# Printing.net
KiCad netlist of a schematic drawn in Altium Designer
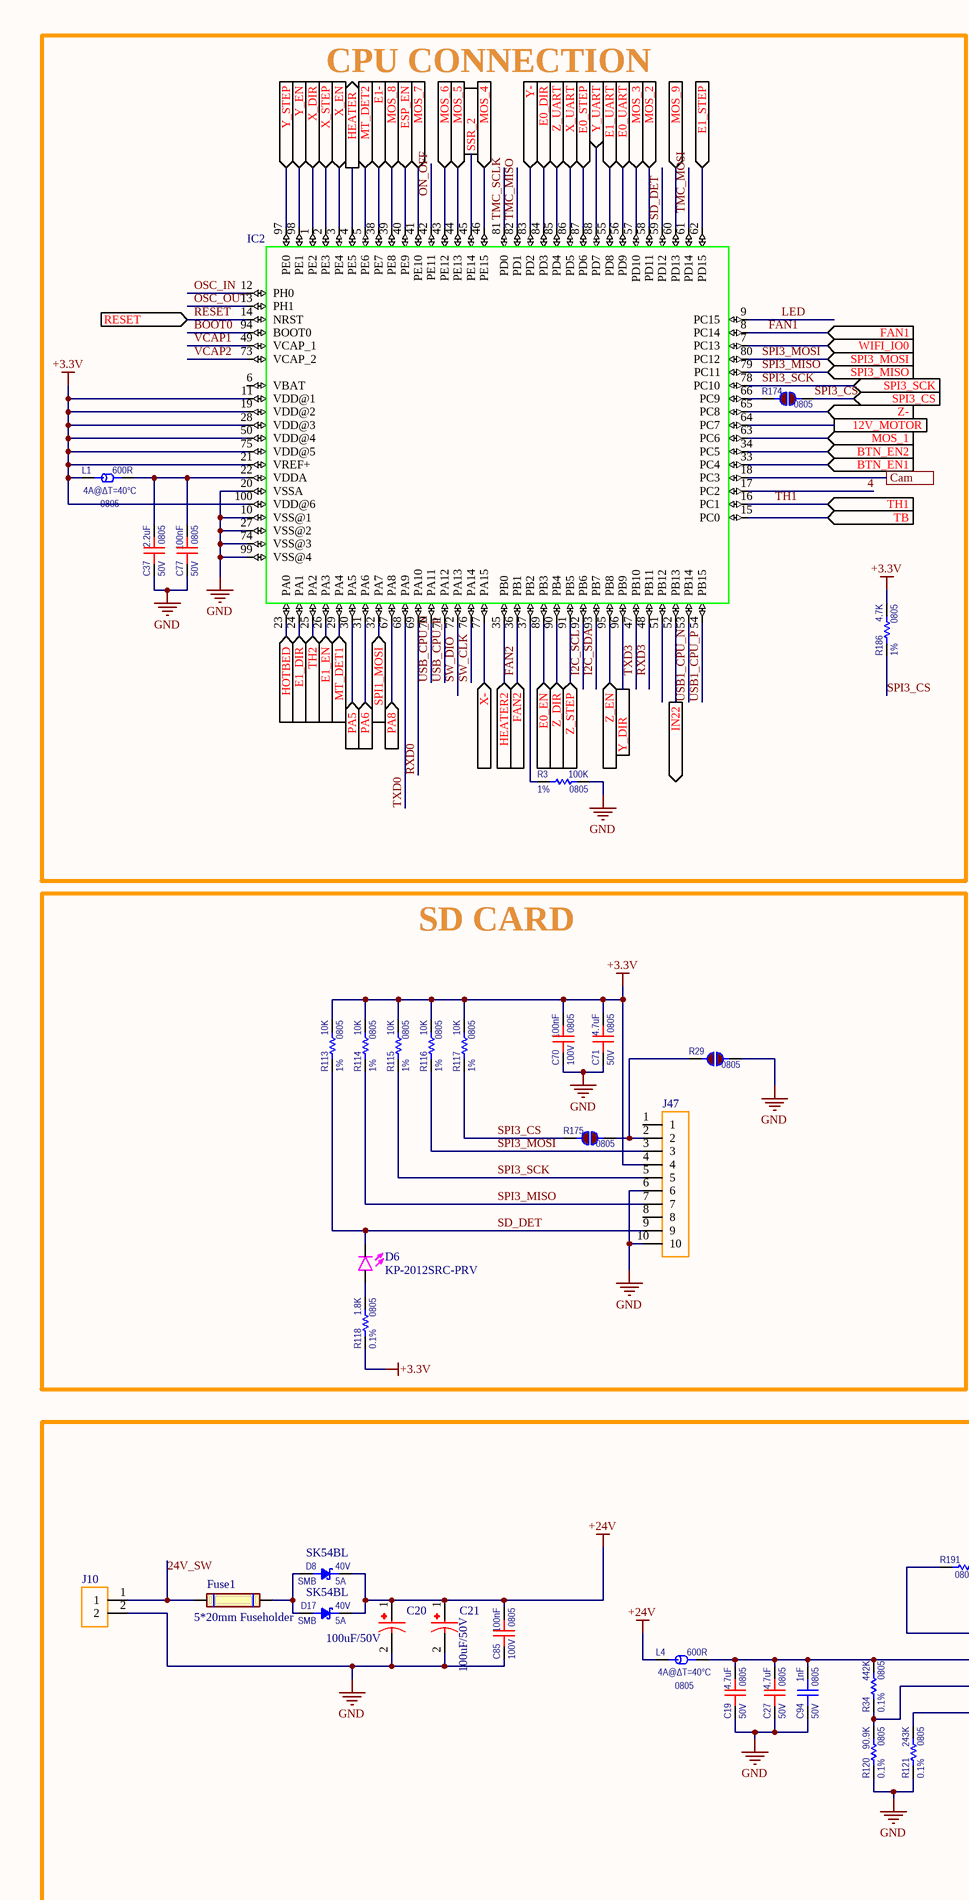
[diagram p0: Printing.SchDoc, left]
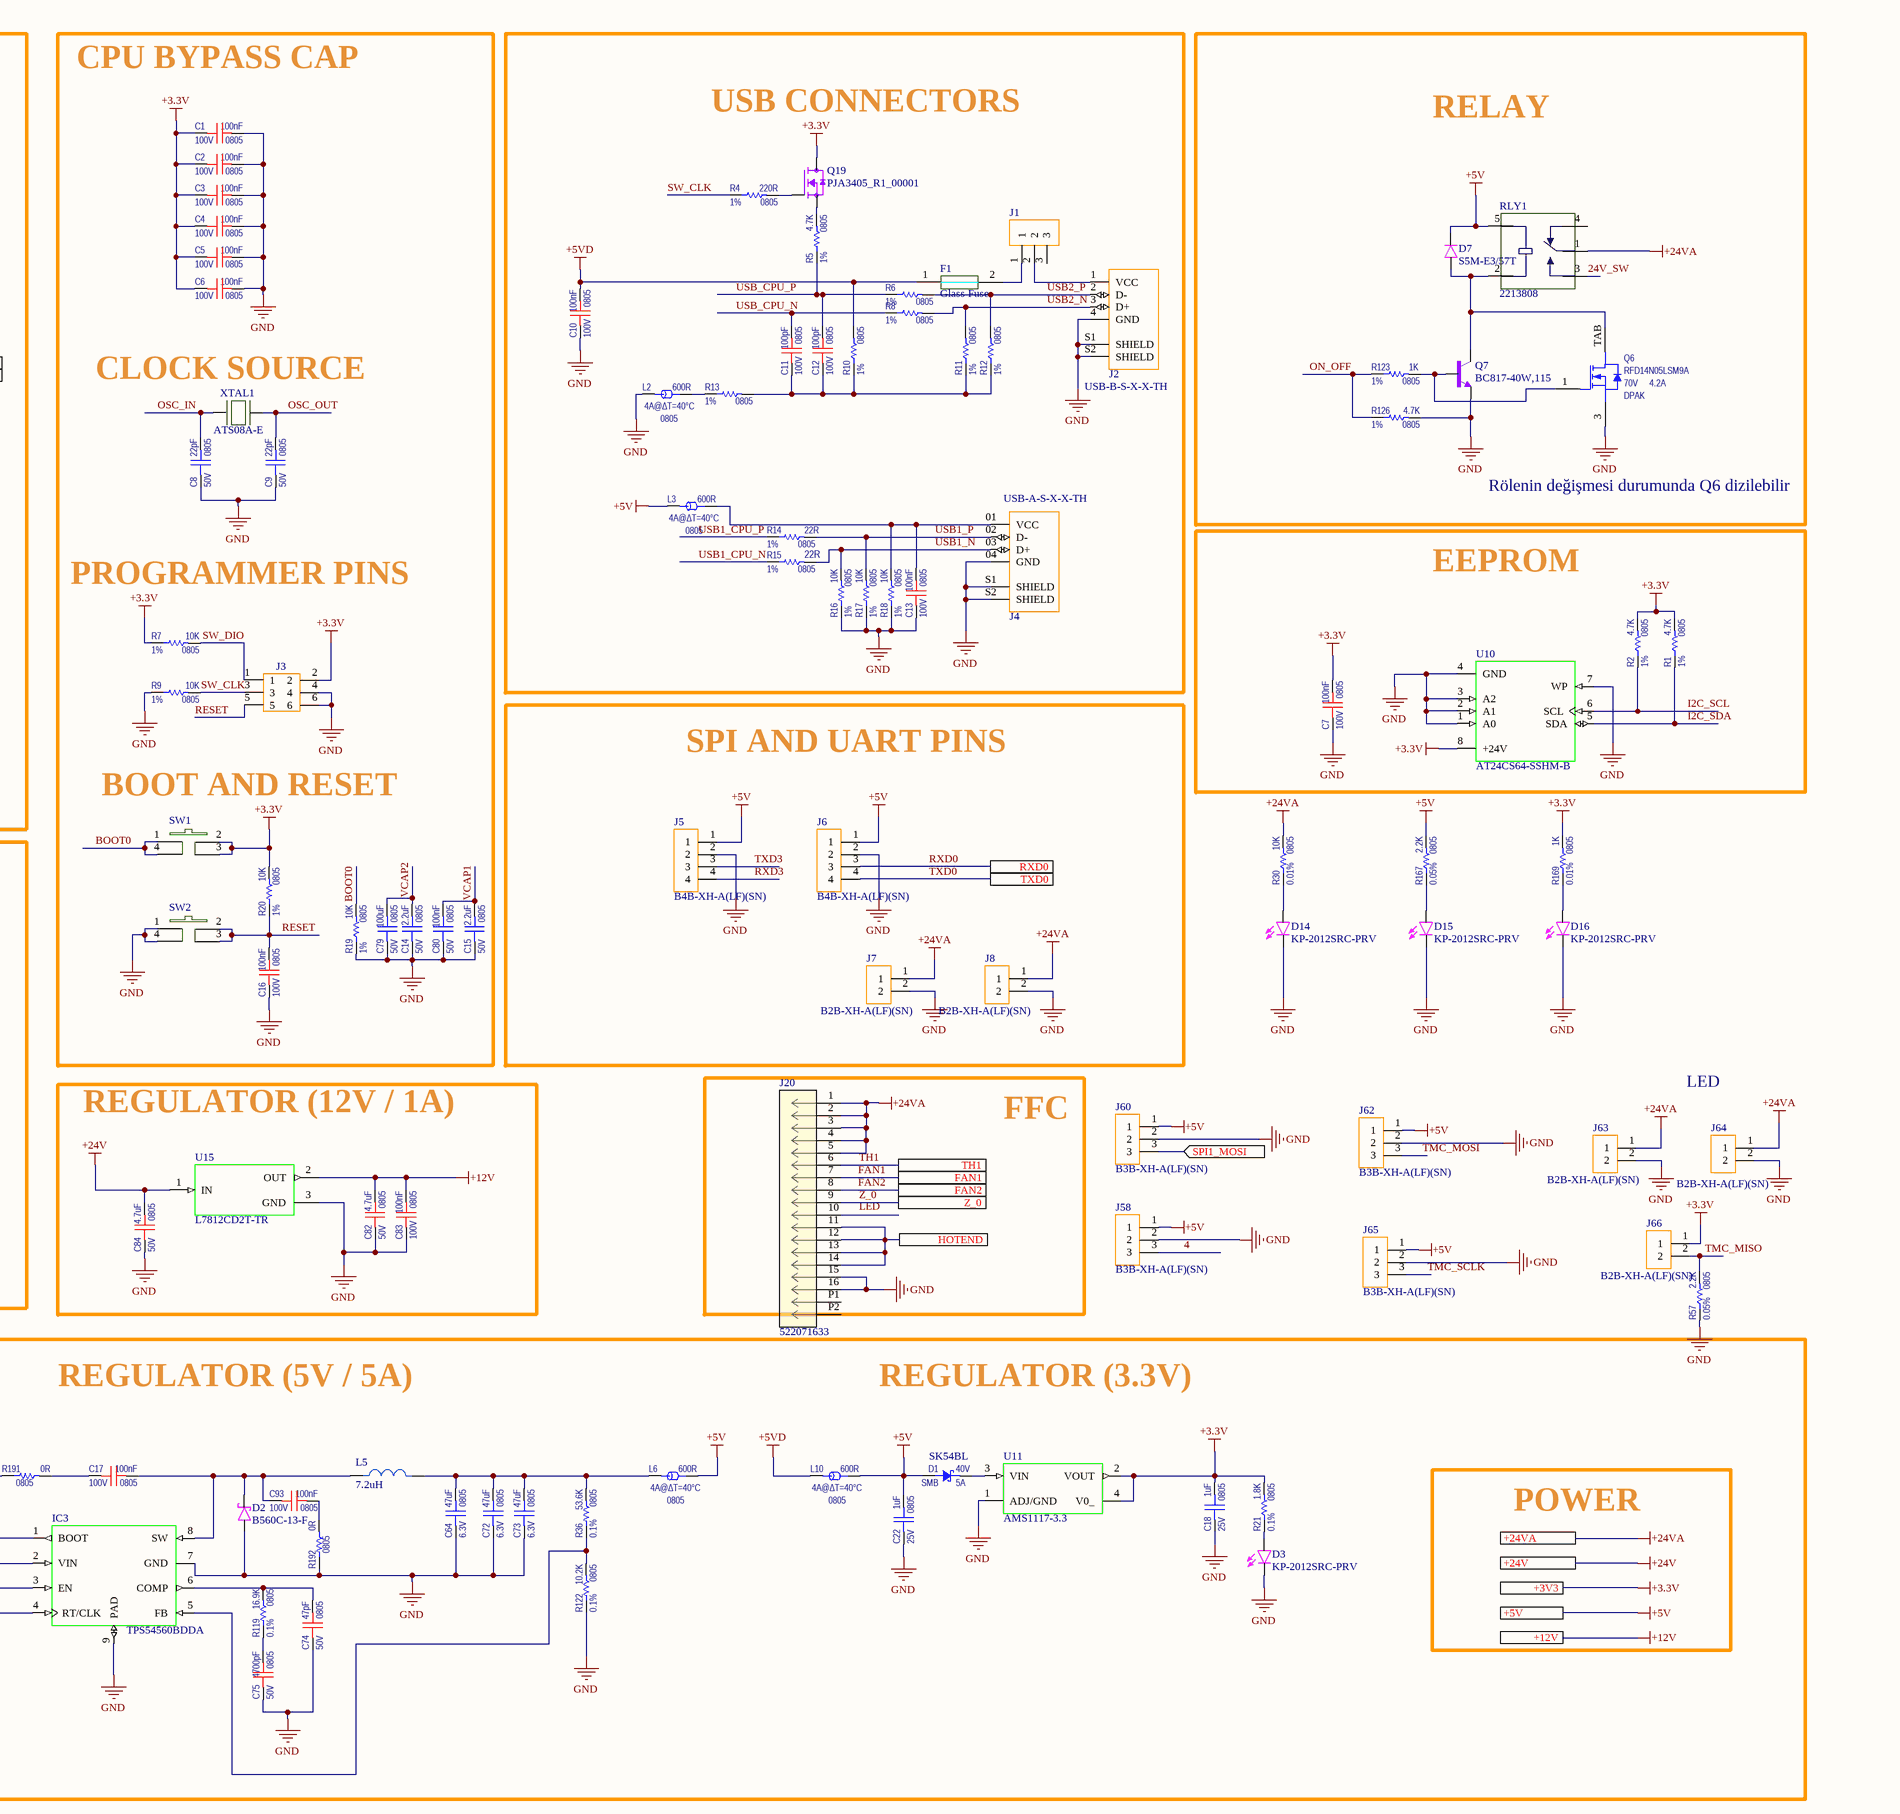
[diagram p1: Printing.SchDoc, right]

(export (version "E")
  (design (tool "Eeschema 10.0.6"))
  (components
    (comp (ref "C1")
      (value "100nF")
      (footprint "C_0805_GEN_1.40H")
      (description "CAP_CER_100nF_100V_X7R_10%_0805")
      (fields
        (field (name "VOLTAGE") "100V")
        (field (name "PACKAGE") "0805")
        (field (name "SIMILAR PART") "C0805C104J1RECAUTO7210; C0805X104J1RECAUTO")
        (field (name "TOLERANCE") "10%")
        (field (name "ADDED BY") "İlhanT")
        (field (name "CHECKED BY") "İlkerU")
      )
      (libsource (lib "FireANTs_HwLibDB") (part "ESDSafeCapacitor"))
    )
    (comp (ref "C2")
      (value "100nF")
      (footprint "C_0805_GEN_1.40H")
      (description "CAP_CER_100nF_100V_X7R_10%_0805")
      (fields
        (field (name "VOLTAGE") "100V")
        (field (name "PACKAGE") "0805")
        (field (name "SIMILAR PART") "C0805C104J1RECAUTO7210; C0805X104J1RECAUTO")
        (field (name "TOLERANCE") "10%")
        (field (name "ADDED BY") "İlhanT")
        (field (name "CHECKED BY") "İlkerU")
      )
      (libsource (lib "FireANTs_HwLibDB") (part "ESDSafeCapacitor"))
    )
    (comp (ref "C3")
      (value "100nF")
      (footprint "C_0805_GEN_1.40H")
      (description "CAP_CER_100nF_100V_X7R_10%_0805")
      (fields
        (field (name "VOLTAGE") "100V")
        (field (name "PACKAGE") "0805")
        (field (name "SIMILAR PART") "C0805C104J1RECAUTO7210; C0805X104J1RECAUTO")
        (field (name "TOLERANCE") "10%")
        (field (name "ADDED BY") "İlhanT")
        (field (name "CHECKED BY") "İlkerU")
      )
      (libsource (lib "FireANTs_HwLibDB") (part "ESDSafeCapacitor"))
    )
    (comp (ref "C4")
      (value "100nF")
      (footprint "C_0805_GEN_1.40H")
      (description "CAP_CER_100nF_100V_X7R_10%_0805")
      (fields
        (field (name "VOLTAGE") "100V")
        (field (name "PACKAGE") "0805")
        (field (name "SIMILAR PART") "C0805C104J1RECAUTO7210; C0805X104J1RECAUTO")
        (field (name "TOLERANCE") "10%")
        (field (name "ADDED BY") "İlhanT")
        (field (name "CHECKED BY") "İlkerU")
      )
      (libsource (lib "FireANTs_HwLibDB") (part "ESDSafeCapacitor"))
    )
    (comp (ref "C5")
      (value "100nF")
      (footprint "C_0805_GEN_1.40H")
      (description "CAP_CER_100nF_100V_X7R_10%_0805")
      (fields
        (field (name "VOLTAGE") "100V")
        (field (name "PACKAGE") "0805")
        (field (name "SIMILAR PART") "C0805C104J1RECAUTO7210; C0805X104J1RECAUTO")
        (field (name "TOLERANCE") "10%")
        (field (name "ADDED BY") "İlhanT")
        (field (name "CHECKED BY") "İlkerU")
      )
      (libsource (lib "FireANTs_HwLibDB") (part "ESDSafeCapacitor"))
    )
    (comp (ref "C6")
      (value "100nF")
      (footprint "C_0805_GEN_1.40H")
      (description "CAP_CER_100nF_100V_X7R_10%_0805")
      (fields
        (field (name "VOLTAGE") "100V")
        (field (name "PACKAGE") "0805")
        (field (name "SIMILAR PART") "C0805C104J1RECAUTO7210; C0805X104J1RECAUTO")
        (field (name "TOLERANCE") "10%")
        (field (name "ADDED BY") "İlhanT")
        (field (name "CHECKED BY") "İlkerU")
      )
      (libsource (lib "FireANTs_HwLibDB") (part "ESDSafeCapacitor"))
    )
    (comp (ref "C7")
      (value "100nF")
      (footprint "C_0805_GEN_1.40H")
      (description "CAP_CER_100nF_100V_X7R_10%_0805")
      (fields
        (field (name "VOLTAGE") "100V")
        (field (name "PACKAGE") "0805")
        (field (name "SIMILAR PART") "C0805C104J1RECAUTO7210; C0805X104J1RECAUTO")
        (field (name "TOLERANCE") "10%")
        (field (name "ADDED BY") "İlhanT")
        (field (name "CHECKED BY") "İlkerU")
      )
      (libsource (lib "FireANTs_HwLibDB") (part "ESDSafeCapacitor"))
    )
    (comp (ref "C8")
      (value "22pF")
      (footprint "C_0805_GEN_1.10H")
      (description "CAP_CER_22pF_50V_X5R_5%_0805")
      (fields
        (field (name "VOLTAGE") "50V")
        (field (name "PACKAGE") "0805")
        (field (name "TOLERANCE") "5%")
        (field (name "Comment") "Capacitor")
        (field (name "ADDED BY") "HicabiB")
        (field (name "CHECKED BY") "???")
      )
      (libsource (lib "FireANTs_HwLibDB") (part "Capacitor"))
    )
    (comp (ref "C9")
      (value "22pF")
      (footprint "C_0805_GEN_1.10H")
      (description "CAP_CER_22pF_50V_X5R_5%_0805")
      (fields
        (field (name "VOLTAGE") "50V")
        (field (name "PACKAGE") "0805")
        (field (name "TOLERANCE") "5%")
        (field (name "Comment") "Capacitor")
        (field (name "ADDED BY") "HicabiB")
        (field (name "CHECKED BY") "???")
      )
      (libsource (lib "FireANTs_HwLibDB") (part "Capacitor"))
    )
    (comp (ref "C10")
      (value "100nF")
      (footprint "C_0805_GEN_1.40H")
      (description "CAP_CER_100nF_100V_X7R_10%_0805")
      (fields
        (field (name "VOLTAGE") "100V")
        (field (name "PACKAGE") "0805")
        (field (name "SIMILAR PART") "C0805C104J1RECAUTO7210; C0805X104J1RECAUTO")
        (field (name "TOLERANCE") "10%")
        (field (name "ADDED BY") "İlhanT")
        (field (name "CHECKED BY") "İlkerU")
      )
      (libsource (lib "FireANTs_HwLibDB") (part "ESDSafeCapacitor"))
    )
    (comp (ref "C11")
      (value "100pF")
      (footprint "C_0805_GEN_1.40H")
      (description "CAP_CER_100nF_100V_X7R_10%_0805")
      (fields
        (field (name "VOLTAGE") "100V")
        (field (name "PACKAGE") "0805")
        (field (name "SIMILAR PART") "C0805C104J1RECAUTO7210; C0805X104J1RECAUTO")
        (field (name "TOLERANCE") "10%")
        (field (name "ADDED BY") "İlhanT")
        (field (name "CHECKED BY") "İlkerU")
      )
      (libsource (lib "FireANTs_HwLibDB") (part "ESDSafeCapacitor"))
    )
    (comp (ref "C12")
      (value "100pF")
      (footprint "C_0805_GEN_1.40H")
      (description "CAP_CER_100nF_100V_X7R_10%_0805")
      (fields
        (field (name "VOLTAGE") "100V")
        (field (name "PACKAGE") "0805")
        (field (name "SIMILAR PART") "C0805C104J1RECAUTO7210; C0805X104J1RECAUTO")
        (field (name "TOLERANCE") "10%")
        (field (name "ADDED BY") "İlhanT")
        (field (name "CHECKED BY") "İlkerU")
      )
      (libsource (lib "FireANTs_HwLibDB") (part "ESDSafeCapacitor"))
    )
    (comp (ref "C13")
      (value "100nF")
      (footprint "C_0805_GEN_1.40H")
      (description "CAP_CER_100nF_100V_X7R_10%_0805")
      (fields
        (field (name "VOLTAGE") "100V")
        (field (name "PACKAGE") "0805")
        (field (name "SIMILAR PART") "C0805C104J1RECAUTO7210; C0805X104J1RECAUTO")
        (field (name "TOLERANCE") "10%")
        (field (name "ADDED BY") "İlhanT")
        (field (name "CHECKED BY") "İlkerU")
      )
      (libsource (lib "FireANTs_HwLibDB") (part "ESDSafeCapacitor"))
    )
    (comp (ref "C14")
      (value "2.2uF")
      (footprint "C_0805_GEN_1.40H")
      (description "CAP_CER_2.2uF_50V_X5R_10%_0805")
      (fields
        (field (name "VOLTAGE") "50V")
        (field (name "PACKAGE") "0805")
        (field (name "TOLERANCE") "10%")
        (field (name "Comment") "Capacitor")
        (field (name "ADDED BY") "HicabiB")
        (field (name "CHECKED BY") "???")
      )
      (libsource (lib "FireANTs_HwLibDB") (part "Capacitor"))
    )
    (comp (ref "C15")
      (value "2.2uF")
      (footprint "C_0805_GEN_1.40H")
      (description "CAP_CER_2.2uF_50V_X5R_10%_0805")
      (fields
        (field (name "VOLTAGE") "50V")
        (field (name "PACKAGE") "0805")
        (field (name "TOLERANCE") "10%")
        (field (name "Comment") "Capacitor")
        (field (name "ADDED BY") "HicabiB")
        (field (name "CHECKED BY") "???")
      )
      (libsource (lib "FireANTs_HwLibDB") (part "Capacitor"))
    )
    (comp (ref "C16")
      (value "100nF")
      (footprint "C_0805_GEN_1.40H")
      (description "CAP_CER_100nF_100V_X7R_10%_0805")
      (fields
        (field (name "VOLTAGE") "100V")
        (field (name "PACKAGE") "0805")
        (field (name "SIMILAR PART") "C0805C104J1RECAUTO7210; C0805X104J1RECAUTO")
        (field (name "TOLERANCE") "10%")
        (field (name "ADDED BY") "İlhanT")
        (field (name "CHECKED BY") "İlkerU")
      )
      (libsource (lib "FireANTs_HwLibDB") (part "ESDSafeCapacitor"))
    )
    (comp (ref "C17")
      (value "100nF")
      (footprint "C_0805_GEN_1.40H")
      (description "CAP_CER_100nF_100V_X7R_10%_0805")
      (fields
        (field (name "VOLTAGE") "100V")
        (field (name "PACKAGE") "0805")
        (field (name "SIMILAR PART") "C0805C104J1RECAUTO7210; C0805X104J1RECAUTO")
        (field (name "TOLERANCE") "10%")
        (field (name "ADDED BY") "İlhanT")
        (field (name "CHECKED BY") "İlkerU")
      )
      (libsource (lib "FireANTs_HwLibDB") (part "ESDSafeCapacitor"))
    )
    (comp (ref "C18")
      (value "1uF")
      (footprint "C_0805_GEN_1.40H")
      (description "CAP_CER_1uF_25V_X7R_10%_0805")
      (fields
        (field (name "VOLTAGE") "25V")
        (field (name "PACKAGE") "0805")
        (field (name "SIMILAR PART") "CGA4J3X7R1E105K125AB")
        (field (name "TOLERANCE") "10%")
        (field (name "ADDED BY") "SonerI")
        (field (name "CHECKED BY") "İlkerU")
      )
      (libsource (lib "FireANTs_HwLibDB") (part "Capacitor"))
    )
    (comp (ref "C19")
      (value "4.7uF")
      (footprint "C_0805_GEN_1.40H")
      (description "CAP_CER_100nF_100V_X7R_10%_0805")
      (fields
        (field (name "VOLTAGE") "50V")
        (field (name "PACKAGE") "0805")
        (field (name "SIMILAR PART") "C0805C104J1RECAUTO7210; C0805X104J1RECAUTO")
        (field (name "TOLERANCE") "10%")
        (field (name "ADDED BY") "İlhanT")
        (field (name "CHECKED BY") "İlkerU")
      )
      (libsource (lib "FireANTs_HwLibDB") (part "ESDSafeCapacitor"))
    )
    (comp (ref "C20")
      (value "100uF/50V")
      (footprint "SC1V107M6L07KVR")
      (libsource (lib "Printing") (part "SC1V107M6L07KVR"))
    )
    (comp (ref "C21")
      (value "100uF/50V")
      (footprint "SC1V107M6L07KVR")
      (libsource (lib "Printing") (part "SC1V107M6L07KVR"))
    )
    (comp (ref "C22")
      (value "1uF")
      (footprint "C_0805_GEN_1.40H")
      (description "CAP_CER_1uF_25V_X7R_10%_0805")
      (fields
        (field (name "VOLTAGE") "25V")
        (field (name "PACKAGE") "0805")
        (field (name "SIMILAR PART") "CGA4J3X7R1E105K125AB")
        (field (name "TOLERANCE") "10%")
        (field (name "ADDED BY") "SonerI")
        (field (name "CHECKED BY") "İlkerU")
      )
      (libsource (lib "FireANTs_HwLibDB") (part "Capacitor"))
    )
    (comp (ref "C27")
      (value "4.7uF")
      (footprint "C_0805_GEN_1.40H")
      (description "CAP_CER_100nF_100V_X7R_10%_0805")
      (fields
        (field (name "VOLTAGE") "50V")
        (field (name "PACKAGE") "0805")
        (field (name "SIMILAR PART") "C0805C104J1RECAUTO7210; C0805X104J1RECAUTO")
        (field (name "TOLERANCE") "10%")
        (field (name "ADDED BY") "İlhanT")
        (field (name "CHECKED BY") "İlkerU")
      )
      (libsource (lib "FireANTs_HwLibDB") (part "ESDSafeCapacitor"))
    )
    (comp (ref "C37")
      (value "2.2uF")
      (footprint "C_0805_GEN_1.40H")
      (description "CAP_CER_100nF_100V_X7R_10%_0805")
      (fields
        (field (name "VOLTAGE") "50V")
        (field (name "PACKAGE") "0805")
        (field (name "SIMILAR PART") "C0805C104J1RECAUTO7210; C0805X104J1RECAUTO")
        (field (name "TOLERANCE") "10%")
        (field (name "ADDED BY") "İlhanT")
        (field (name "CHECKED BY") "İlkerU")
      )
      (libsource (lib "FireANTs_HwLibDB") (part "ESDSafeCapacitor"))
    )
    (comp (ref "C64")
      (value "47uF")
      (footprint "C_0805_GEN_1.40H")
      (description "CAP_CER_47uF_6.3V_X5R_20%_0805")
      (fields
        (field (name "VOLTAGE") "6.3V")
        (field (name "PACKAGE") "0805")
        (field (name "SIMILAR PART") "JMK212BBJ476MG-T")
        (field (name "TOLERANCE") "20%")
        (field (name "ADDED BY") "HasanA")
        (field (name "CHECKED BY") "İlkerU")
      )
      (libsource (lib "FireANTs_HwLibDB") (part "Capacitor"))
    )
    (comp (ref "C70")
      (value "100nF")
      (footprint "C_0805_GEN_1.40H")
      (description "CAP_CER_100nF_100V_X7R_10%_0805")
      (fields
        (field (name "VOLTAGE") "100V")
        (field (name "PACKAGE") "0805")
        (field (name "SIMILAR PART") "C0805C104J1RECAUTO7210; C0805X104J1RECAUTO")
        (field (name "TOLERANCE") "10%")
        (field (name "ADDED BY") "İlhanT")
        (field (name "CHECKED BY") "İlkerU")
      )
      (libsource (lib "FireANTs_HwLibDB") (part "ESDSafeCapacitor"))
    )
    (comp (ref "C71")
      (value "4.7uF")
      (footprint "C_0805_GEN_1.40H")
      (description "CAP_CER_100nF_100V_X7R_10%_0805")
      (fields
        (field (name "VOLTAGE") "50V")
        (field (name "PACKAGE") "0805")
        (field (name "SIMILAR PART") "C0805C104J1RECAUTO7210; C0805X104J1RECAUTO")
        (field (name "TOLERANCE") "10%")
        (field (name "ADDED BY") "İlhanT")
        (field (name "CHECKED BY") "İlkerU")
      )
      (libsource (lib "FireANTs_HwLibDB") (part "ESDSafeCapacitor"))
    )
    (comp (ref "C72")
      (value "47uF")
      (footprint "C_0805_GEN_1.40H")
      (description "CAP_CER_47uF_6.3V_X5R_20%_0805")
      (fields
        (field (name "VOLTAGE") "6.3V")
        (field (name "PACKAGE") "0805")
        (field (name "SIMILAR PART") "JMK212BBJ476MG-T")
        (field (name "TOLERANCE") "20%")
        (field (name "ADDED BY") "HasanA")
        (field (name "CHECKED BY") "İlkerU")
      )
      (libsource (lib "FireANTs_HwLibDB") (part "Capacitor"))
    )
    (comp (ref "C73")
      (value "47uF")
      (footprint "C_0805_GEN_1.40H")
      (description "CAP_CER_47uF_6.3V_X5R_20%_0805")
      (fields
        (field (name "VOLTAGE") "6.3V")
        (field (name "PACKAGE") "0805")
        (field (name "SIMILAR PART") "JMK212BBJ476MG-T")
        (field (name "TOLERANCE") "20%")
        (field (name "ADDED BY") "HasanA")
        (field (name "CHECKED BY") "İlkerU")
      )
      (libsource (lib "FireANTs_HwLibDB") (part "Capacitor"))
    )
    (comp (ref "C74")
      (value "47pF")
      (footprint "C_0805_GEN_1.40H")
      (description "CAP_CER_100nF_100V_X7R_10%_0805")
      (fields
        (field (name "VOLTAGE") "50V")
        (field (name "PACKAGE") "0805")
        (field (name "SIMILAR PART") "C0805C104J1RECAUTO7210; C0805X104J1RECAUTO")
        (field (name "TOLERANCE") "10%")
        (field (name "ADDED BY") "İlhanT")
        (field (name "CHECKED BY") "İlkerU")
      )
      (libsource (lib "FireANTs_HwLibDB") (part "ESDSafeCapacitor"))
    )
    (comp (ref "C75")
      (value "4700pF")
      (footprint "C_0805_GEN_1.40H")
      (description "CAP_CER_100nF_100V_X7R_10%_0805")
      (fields
        (field (name "VOLTAGE") "50V")
        (field (name "PACKAGE") "0805")
        (field (name "SIMILAR PART") "C0805C104J1RECAUTO7210; C0805X104J1RECAUTO")
        (field (name "TOLERANCE") "10%")
        (field (name "ADDED BY") "İlhanT")
        (field (name "CHECKED BY") "İlkerU")
      )
      (libsource (lib "FireANTs_HwLibDB") (part "ESDSafeCapacitor"))
    )
    (comp (ref "C77")
      (value "100nF")
      (footprint "C_0805_GEN_1.40H")
      (description "CAP_CER_100nF_100V_X7R_10%_0805")
      (fields
        (field (name "VOLTAGE") "50V")
        (field (name "PACKAGE") "0805")
        (field (name "SIMILAR PART") "C0805C104J1RECAUTO7210; C0805X104J1RECAUTO")
        (field (name "TOLERANCE") "10%")
        (field (name "ADDED BY") "İlhanT")
        (field (name "CHECKED BY") "İlkerU")
      )
      (libsource (lib "FireANTs_HwLibDB") (part "ESDSafeCapacitor"))
    )
    (comp (ref "C79")
      (value "100uF")
      (footprint "C_0805_GEN_1.40H")
      (description "CAP_CER_2.2uF_50V_X5R_10%_0805")
      (fields
        (field (name "VOLTAGE") "50V")
        (field (name "PACKAGE") "0805")
        (field (name "TOLERANCE") "10%")
        (field (name "Comment") "Capacitor")
        (field (name "ADDED BY") "HicabiB")
        (field (name "CHECKED BY") "???")
      )
      (libsource (lib "FireANTs_HwLibDB") (part "Capacitor"))
    )
    (comp (ref "C80")
      (value "100nF")
      (footprint "C_0805_GEN_1.40H")
      (description "CAP_CER_2.2uF_50V_X5R_10%_0805")
      (fields
        (field (name "VOLTAGE") "50V")
        (field (name "PACKAGE") "0805")
        (field (name "TOLERANCE") "10%")
        (field (name "Comment") "Capacitor")
        (field (name "ADDED BY") "HicabiB")
        (field (name "CHECKED BY") "???")
      )
      (libsource (lib "FireANTs_HwLibDB") (part "Capacitor"))
    )
    (comp (ref "C82")
      (value "4.7uF")
      (footprint "C_0805_GEN_1.40H")
      (description "CAP_CER_100nF_100V_X7R_10%_0805")
      (fields
        (field (name "VOLTAGE") "50V")
        (field (name "PACKAGE") "0805")
        (field (name "SIMILAR PART") "C0805C104J1RECAUTO7210; C0805X104J1RECAUTO")
        (field (name "TOLERANCE") "10%")
        (field (name "ADDED BY") "İlhanT")
        (field (name "CHECKED BY") "İlkerU")
      )
      (libsource (lib "FireANTs_HwLibDB") (part "ESDSafeCapacitor"))
    )
    (comp (ref "C83")
      (value "100nF")
      (footprint "C_0805_GEN_1.40H")
      (description "CAP_CER_100nF_100V_X7R_10%_0805")
      (fields
        (field (name "VOLTAGE") "100V")
        (field (name "PACKAGE") "0805")
        (field (name "SIMILAR PART") "C0805C104J1RECAUTO7210; C0805X104J1RECAUTO")
        (field (name "TOLERANCE") "10%")
        (field (name "ADDED BY") "İlhanT")
        (field (name "CHECKED BY") "İlkerU")
      )
      (libsource (lib "FireANTs_HwLibDB") (part "ESDSafeCapacitor"))
    )
    (comp (ref "C84")
      (value "4.7uF")
      (footprint "C_0805_GEN_1.40H")
      (description "CAP_CER_100nF_100V_X7R_10%_0805")
      (fields
        (field (name "VOLTAGE") "50V")
        (field (name "PACKAGE") "0805")
        (field (name "SIMILAR PART") "C0805C104J1RECAUTO7210; C0805X104J1RECAUTO")
        (field (name "TOLERANCE") "10%")
        (field (name "ADDED BY") "İlhanT")
        (field (name "CHECKED BY") "İlkerU")
      )
      (libsource (lib "FireANTs_HwLibDB") (part "ESDSafeCapacitor"))
    )
    (comp (ref "C85")
      (value "100nF")
      (footprint "C_0805_GEN_1.40H")
      (description "CAP_CER_100nF_100V_X7R_10%_0805")
      (fields
        (field (name "VOLTAGE") "100V")
        (field (name "PACKAGE") "0805")
        (field (name "SIMILAR PART") "C0805C104J1RECAUTO7210; C0805X104J1RECAUTO")
        (field (name "TOLERANCE") "10%")
        (field (name "ADDED BY") "İlhanT")
        (field (name "CHECKED BY") "İlkerU")
      )
      (libsource (lib "FireANTs_HwLibDB") (part "ESDSafeCapacitor"))
    )
    (comp (ref "C93")
      (value "100nF")
      (footprint "C_0805_GEN_1.40H")
      (description "CAP_CER_100nF_100V_X7R_10%_0805")
      (fields
        (field (name "VOLTAGE") "100V")
        (field (name "PACKAGE") "0805")
        (field (name "SIMILAR PART") "C0805C104J1RECAUTO7210; C0805X104J1RECAUTO")
        (field (name "TOLERANCE") "10%")
        (field (name "ADDED BY") "İlhanT")
        (field (name "CHECKED BY") "İlkerU")
      )
      (libsource (lib "FireANTs_HwLibDB") (part "ESDSafeCapacitor"))
    )
    (comp (ref "C94")
      (value "1nF")
      (footprint "C_0805_GEN_0.70H")
      (description "CAP_CER_1nF_50V_NP0_1%_0805")
      (fields
        (field (name "VOLTAGE") "50V")
        (field (name "PACKAGE") "0805")
        (field (name "SIMILAR PART") "08055A102FAT2A")
        (field (name "TOLERANCE") "1%")
        (field (name "ADDED BY") "İlhanT")
        (field (name "CHECKED BY") "İlkerU")
      )
      (libsource (lib "FireANTs_HwLibDB") (part "Capacitor"))
    )
    (comp (ref "D1")
      (value "SK54BL")
      (footprint "SMB_NRVBS360BT3G")
      (description "DIO_SCHO_SING_60V_3A_SMB")
      (fields
        (field (name "VOLTAGE") "40V")
        (field (name "CURRENT") "5A")
        (field (name "PACKAGE") "SMB")
        (field (name "SIMILAR PART") "STPS3H100UFY")
        (field (name "TOLERANCE") "X")
        (field (name "ADDED BY") "SonerI")
        (field (name "CHECKED BY") "ErayC")
      )
      (libsource (lib "FireANTs_HwLibDB") (part "SchDiode_A2C1"))
    )
    (comp (ref "D2")
      (value "B560C-13-F")
      (footprint "B560C-13-F")
      (description "VR=60V IF=5A 300pF")
      (fields (field (name "MANUFACTURER") "Diodes"))
      (libsource (lib "Printing") (part "B560C-13-F"))
    )
    (comp (ref "D3")
      (value "KP-2012SRC-PRV")
      (footprint "0805 LED")
      (description "KP-2012SRC-PRV Red LED, 640 nm 2012 (0805), Rectangle Lens SMD package")
      (fields (field (name "MANUFACTURER") "Kingbright"))
      (libsource (lib "Printing") (part "KP-2012SRC-PRV"))
    )
    (comp (ref "D6")
      (value "KP-2012SRC-PRV")
      (footprint "0805 LED")
      (description "KP-2012SRC-PRV Red LED, 640 nm 2012 (0805), Rectangle Lens SMD package")
      (fields (field (name "MANUFACTURER") "Kingbright"))
      (libsource (lib "Printing") (part "KP-2012SRC-PRV"))
    )
    (comp (ref "D7")
      (value "S5M-E3/57T")
      (footprint "B560C-13-F")
      (fields (field (name "MANUFACTURER") "Vishay Semiconductors") (field (name "VOLTAGE") "1kV"))
      (libsource (lib "Printing") (part "S5M-E3/57T"))
    )
    (comp (ref "D8")
      (value "SK54BL")
      (footprint "SMB_NRVBS360BT3G")
      (description "DIO_SCHO_SING_60V_3A_SMB")
      (fields
        (field (name "VOLTAGE") "40V")
        (field (name "CURRENT") "5A")
        (field (name "PACKAGE") "SMB")
        (field (name "SIMILAR PART") "STPS3H100UFY")
        (field (name "TOLERANCE") "X")
        (field (name "ADDED BY") "SonerI")
        (field (name "CHECKED BY") "ErayC")
      )
      (libsource (lib "FireANTs_HwLibDB") (part "SchDiode_A2C1"))
    )
    (comp (ref "D14")
      (value "KP-2012SRC-PRV")
      (footprint "0805 LED")
      (description "KP-2012SRC-PRV Red LED, 640 nm 2012 (0805), Rectangle Lens SMD package")
      (fields (field (name "MANUFACTURER") "Kingbright"))
      (libsource (lib "Printing") (part "KP-2012SRC-PRV"))
    )
    (comp (ref "D15")
      (value "KP-2012SRC-PRV")
      (footprint "0805 LED")
      (description "KP-2012SRC-PRV Red LED, 640 nm 2012 (0805), Rectangle Lens SMD package")
      (fields (field (name "MANUFACTURER") "Kingbright"))
      (libsource (lib "Printing") (part "KP-2012SRC-PRV"))
    )
    (comp (ref "D16")
      (value "KP-2012SRC-PRV")
      (footprint "0805 LED")
      (description "KP-2012SRC-PRV Red LED, 640 nm 2012 (0805), Rectangle Lens SMD package")
      (fields (field (name "MANUFACTURER") "Kingbright"))
      (libsource (lib "Printing") (part "KP-2012SRC-PRV"))
    )
    (comp (ref "D17")
      (value "SK54BL")
      (footprint "SMB_NRVBS360BT3G")
      (description "DIO_SCHO_SING_60V_3A_SMB")
      (fields
        (field (name "VOLTAGE") "40V")
        (field (name "CURRENT") "5A")
        (field (name "PACKAGE") "SMB")
        (field (name "SIMILAR PART") "STPS3H100UFY")
        (field (name "TOLERANCE") "X")
        (field (name "ADDED BY") "SonerI")
        (field (name "CHECKED BY") "ErayC")
      )
      (libsource (lib "FireANTs_HwLibDB") (part "SchDiode_A2C1"))
    )
    (comp (ref "F1")
      (value "Glass Fuse")
      (footprint "2410 Sigorta")
      (libsource (lib "Printing") (part "Glass Fuse"))
    )
    (comp (ref "Fuse1")
      (value "5*20mm Fuseholder")
      (footprint "696310001002")
      (description "Fuse Holder 20 A 250V 1 Circuit Cartridge Through Hole")
      (fields (field (name "MF") "Wurth Elektronik") (field (name "MP") "696310001002"))
      (libsource (lib "Printing") (part "696310001002"))
    )
    (comp (ref "IC2")
      (value "MCU-STM32F407VET6(LQFP100)")
      (footprint "LQFP100-0.5-13.8X13.8MM")
      (description "ARMÂ® CortexÂ®-M4 STM32F4 Microcontroller IC 32-Bit 168MHz 512KB _512K x 8_ FLASH 100-LQFP _14x14_")
      (fields (field (name "MF") "STMicroelectronics") (field (name "MP") "STM32F407VET6"))
      (libsource (lib "Printing") (part "MCU-STM32F407VET6(LQFP100)"))
    )
    (comp (ref "IC3")
      (value "TPS54560BDDA")
      (footprint "VREG_LM5017MR/NOPB")
      (description "4.5-V to 60-V input, 5-A, step-down DC-DC converter with Eco-mode 8-SO PowerPAD -40 to 150")
      (fields (field (name "MF") "Texas Instruments"))
      (libsource (lib "Printing") (part "TPS54560BDDA"))
    )
    (comp (ref "J1")
      (value "L-KLS1-207-1-03-S")
      (footprint "L-KLS1-207-1-03-S")
      (libsource (lib "Printing") (part "L-KLS1-207-1-03-S"))
    )
    (comp (ref "J2")
      (value "USB-B-S-X-X-TH")
      (footprint "SAMTEC_USB-B-S-X-X-TH")
      (description "USB-B (USB TYPE-B) USB 2.0 Receptacle Connector 4 Position Through Hole, Right Angle")
      (libsource (lib "Printing") (part "USB-B-S-X-X-TH"))
    )
    (comp (ref "J3")
      (value "5PH1SDA25-203G0NNBL-3X6")
      (footprint "5PH1SDA25-203G0NNBL-3X6")
      (libsource (lib "Printing") (part "5PH1SDA25-203G0NNBL-3X6"))
    )
    (comp (ref "J4")
      (value "USB-A-S-X-X-TH")
      (footprint "SAMTEC_USB-A-S-X-X-TH")
      (description "USB-A (USB TYPE-A) USB 2.0 Receptacle Connector 4 Position Through Hole, Right Angle")
      (fields (field (name "MP") "USB-A-S-S-W-TH") (field (name "DIGI-KEY_PART_NUMBER") "SAM10373-ND"))
      (libsource (lib "Printing") (part "USB-A-S-X-X-TH"))
    )
    (comp (ref "J5")
      (value "B4B-XH-A(LF)(SN)")
      (footprint "JST_B4B-XH-A(LF)(SN)")
      (libsource (lib "Printing") (part "B4B-XH-A(LF)(SN)"))
    )
    (comp (ref "J6")
      (value "B4B-XH-A(LF)(SN)")
      (footprint "JST_B4B-XH-A(LF)(SN)")
      (libsource (lib "Printing") (part "B4B-XH-A(LF)(SN)"))
    )
    (comp (ref "J7")
      (value "B2B-XH-A(LF)(SN)")
      (footprint "JST_B2B-XH-A(LF)(SN)")
      (description "Connector Header Through Hole 2 position 0.098 (2.50mm)")
      (fields (field (name "MF") "JST Sales"))
      (libsource (lib "Printing") (part "B2B-XH-A(LF)(SN)"))
    )
    (comp (ref "J8")
      (value "B2B-XH-A(LF)(SN)")
      (footprint "JST_B2B-XH-A(LF)(SN)")
      (description "Connector Header Through Hole 2 position 0.098 (2.50mm)")
      (fields (field (name "MF") "JST Sales"))
      (libsource (lib "Printing") (part "B2B-XH-A(LF)(SN)"))
    )
    (comp (ref "J10")
      (value "5.08 Klemens")
      (footprint "5.08 Klemens")
      (libsource (lib "Printing") (part "5.08 Klemens"))
    )
    (comp (ref "J20")
      (value "522071633")
      (footprint "CON_522071633_MOL")
      (description "No Description Available")
      (libsource (lib "Printing") (part "522071633"))
    )
    (comp (ref "J47")
      (value "BH10B-XH-2(LF)(SN)")
      (footprint "BH10B-XH-2(LF)(SN)")
      (description "Connector Header, XH Series, 10 Position, 2.5mm, 250V, Through Hole, Press Fit, Solder, Natural")
      (fields (field (name "MANUFACTURER") "JST"))
      (libsource (lib "Printing") (part "BH10B-XH-2(LF)(SN)"))
    )
    (comp (ref "J58")
      (value "B3B-XH-A(LF)(SN)")
      (footprint "JST_B3B-XH-A(LF)(SN)")
      (libsource (lib "Printing") (part "B3B-XH-A(LF)(SN)"))
    )
    (comp (ref "J60")
      (value "B3B-XH-A(LF)(SN)")
      (footprint "JST_B3B-XH-A(LF)(SN)")
      (libsource (lib "Printing") (part "B3B-XH-A(LF)(SN)"))
    )
    (comp (ref "J62")
      (value "B3B-XH-A(LF)(SN)")
      (footprint "JST_B3B-XH-A(LF)(SN)")
      (libsource (lib "Printing") (part "B3B-XH-A(LF)(SN)"))
    )
    (comp (ref "J63")
      (value "B2B-XH-A(LF)(SN)")
      (footprint "JST_B2B-XH-A(LF)(SN)")
      (description "Connector Header Through Hole 2 position 0.098 (2.50mm)")
      (fields (field (name "MF") "JST Sales"))
      (libsource (lib "Printing") (part "B2B-XH-A(LF)(SN)"))
    )
    (comp (ref "J64")
      (value "B2B-XH-A(LF)(SN)")
      (footprint "JST_B2B-XH-A(LF)(SN)")
      (description "Connector Header Through Hole 2 position 0.098 (2.50mm)")
      (fields (field (name "MF") "JST Sales"))
      (libsource (lib "Printing") (part "B2B-XH-A(LF)(SN)"))
    )
    (comp (ref "J65")
      (value "B3B-XH-A(LF)(SN)")
      (footprint "JST_B3B-XH-A(LF)(SN)")
      (libsource (lib "Printing") (part "B3B-XH-A(LF)(SN)"))
    )
    (comp (ref "J66")
      (value "B2B-XH-A(LF)(SN)")
      (footprint "JST_B2B-XH-A(LF)(SN)")
      (description "Connector Header Through Hole 2 position 0.098 (2.50mm)")
      (fields (field (name "MF") "JST Sales"))
      (libsource (lib "Printing") (part "B2B-XH-A(LF)(SN)"))
    )
    (comp (ref "L1")
      (value "600R")
      (footprint "FB_0805_GEN_1.10H")
      (description "IND_FER_600R@100M_2A_25%_0805")
      (fields
        (field (name "CURRENT") "4A@ΔT=40°C")
        (field (name "PACKAGE") "0805")
        (field (name "TOLERANCE") "±25%")
        (field (name "VOLTAGE") "X")
        (field (name "ADDED BY") "HasanA")
        (field (name "CHECKED BY") "ErayC")
      )
      (libsource (lib "FireANTs_HwLibDB") (part "FerriteBead"))
    )
    (comp (ref "L2")
      (value "600R")
      (footprint "FB_0805_GEN_1.10H")
      (description "IND_FER_600R@100M_2A_25%_0805")
      (fields
        (field (name "CURRENT") "4A@ΔT=40°C")
        (field (name "PACKAGE") "0805")
        (field (name "TOLERANCE") "±25%")
        (field (name "VOLTAGE") "X")
        (field (name "ADDED BY") "HasanA")
        (field (name "CHECKED BY") "ErayC")
      )
      (libsource (lib "FireANTs_HwLibDB") (part "FerriteBead"))
    )
    (comp (ref "L3")
      (value "600R")
      (footprint "FB_0805_GEN_1.10H")
      (description "IND_FER_600R@100M_2A_25%_0805")
      (fields
        (field (name "CURRENT") "4A@ΔT=40°C")
        (field (name "PACKAGE") "0805")
        (field (name "TOLERANCE") "±25%")
        (field (name "VOLTAGE") "X")
        (field (name "ADDED BY") "HasanA")
        (field (name "CHECKED BY") "ErayC")
      )
      (libsource (lib "FireANTs_HwLibDB") (part "FerriteBead"))
    )
    (comp (ref "L4")
      (value "600R")
      (footprint "FB_0805_GEN_1.10H")
      (description "IND_FER_600R@100M_2A_25%_0805")
      (fields
        (field (name "CURRENT") "4A@ΔT=40°C")
        (field (name "PACKAGE") "0805")
        (field (name "TOLERANCE") "±25%")
        (field (name "VOLTAGE") "X")
        (field (name "ADDED BY") "HasanA")
        (field (name "CHECKED BY") "ErayC")
      )
      (libsource (lib "FireANTs_HwLibDB") (part "FerriteBead"))
    )
    (comp (ref "L5")
      (value "7.2uH")
      (footprint "7447798720")
      (description "Fixed Ind 7.2UH 7.9A 12.8 Mohm")
      (fields
        (field (name "MANUFACTURER") "Wurth Electronics")
        (field (name "MANUFACTURER PART NUMBER") "7447798720")
      )
      (libsource (lib "Printing") (part "7447798720"))
    )
    (comp (ref "L6")
      (value "600R")
      (footprint "FB_0805_GEN_1.10H")
      (description "IND_FER_600R@100M_2A_25%_0805")
      (fields
        (field (name "CURRENT") "4A@ΔT=40°C")
        (field (name "PACKAGE") "0805")
        (field (name "TOLERANCE") "±25%")
        (field (name "VOLTAGE") "X")
        (field (name "ADDED BY") "HasanA")
        (field (name "CHECKED BY") "ErayC")
      )
      (libsource (lib "FireANTs_HwLibDB") (part "FerriteBead"))
    )
    (comp (ref "L10")
      (value "600R")
      (footprint "FB_0805_GEN_1.10H")
      (description "IND_FER_600R@100M_2A_25%_0805")
      (fields
        (field (name "CURRENT") "4A@ΔT=40°C")
        (field (name "PACKAGE") "0805")
        (field (name "TOLERANCE") "±25%")
        (field (name "VOLTAGE") "X")
        (field (name "ADDED BY") "HasanA")
        (field (name "CHECKED BY") "ErayC")
      )
      (libsource (lib "FireANTs_HwLibDB") (part "FerriteBead"))
    )
    (comp (ref "Q6")
      (value "RFD14N05LSM9A")
      (footprint "DPAK_SQD50N10-8M9L")
      (description "TRA_NMOS_SING_100V_50A_TH2V_DPAK")
      (fields
        (field (name "CURRENT") "4.2A")
        (field (name "VOLTAGE") "70V")
        (field (name "PACKAGE") "DPAK")
        (field (name "SIMILAR PART") "SQM70060EL_GE3; SQM100N10-10_GE3")
        (field (name "TOLERANCE") "X")
        (field (name "ADDED BY") "İlhanT")
        (field (name "CHECKED BY") "YasinY")
      )
      (libsource (lib "FireANTs_HwLibDB") (part "SingleNMOS_G1S3DTAB"))
    )
    (comp (ref "Q7")
      (value "BC817-40W,115")
      (footprint "BC817-40W,115")
      (description "NPN Ic=500mA Vceo=45V hfe=250~600 P=250mW")
      (fields (field (name "MANUFACTURER") "Nexperia"))
      (libsource (lib "Printing") (part "BC817-40W,115"))
    )
    (comp (ref "Q19")
      (value "PJA3405_R1_00001")
      (footprint "PJA3405_R1_00001")
      (fields (field (name "MANUFACTURER") "Pan Jit"))
      (libsource (lib "Printing") (part "PJA3405_R1_00001"))
    )
    (comp (ref "R1")
      (value "4.7K")
      (footprint "R_0805_GEN_0.60H")
      (description "RES_STD_4.7K_0.125W_1%_100ppm_0805")
      (fields
        (field (name "TOLERANCE") "1%")
        (field (name "PACKAGE") "0805")
        (field (name "VOLTAGE") "150V")
        (field (name "Comment") "StandardResistor")
        (field (name "ADDED BY") "SonerI")
        (field (name "CHECKED BY") "YasinY")
      )
      (libsource (lib "FireANTs_HwLibDB") (part "StandardResistor"))
    )
    (comp (ref "R2")
      (value "4.7K")
      (footprint "R_0805_GEN_0.60H")
      (description "RES_STD_4.7K_0.125W_1%_100ppm_0805")
      (fields
        (field (name "TOLERANCE") "1%")
        (field (name "PACKAGE") "0805")
        (field (name "VOLTAGE") "150V")
        (field (name "Comment") "StandardResistor")
        (field (name "ADDED BY") "SonerI")
        (field (name "CHECKED BY") "YasinY")
      )
      (libsource (lib "FireANTs_HwLibDB") (part "StandardResistor"))
    )
    (comp (ref "R3")
      (value "100K")
      (footprint "R_0805_GEN_0.70H")
      (description "RES_STD_100K_0.125W_1%_100ppm_0805")
      (fields
        (field (name "TOLERANCE") "1%")
        (field (name "PACKAGE") "0805")
        (field (name "SIMILAR PART") "ERJ-PB6D1003V; RT0805DRE07100KL")
        (field (name "VOLTAGE") "150V")
        (field (name "ADDED BY") "SonerI")
        (field (name "CHECKED BY") "YasinY")
      )
      (libsource (lib "FireANTs_HwLibDB") (part "StandardResistor"))
    )
    (comp (ref "R4")
      (value "220R")
      (footprint "R_0805_GEN_0.60H")
      (description "RES_STD_220R_0.125W_1%_100ppm_0805")
      (fields
        (field (name "TOLERANCE") "1%")
        (field (name "PACKAGE") "0805")
        (field (name "VOLTAGE") "150V")
        (field (name "Comment") "StandardResistor")
        (field (name "ADDED BY") "HicabiB")
        (field (name "CHECKED BY") "???")
      )
      (libsource (lib "FireANTs_HwLibDB") (part "StandardResistor"))
    )
    (comp (ref "R5")
      (value "4.7K")
      (footprint "R_0805_GEN_0.60H")
      (description "RES_STD_4.7K_0.125W_1%_100ppm_0805")
      (fields
        (field (name "TOLERANCE") "1%")
        (field (name "PACKAGE") "0805")
        (field (name "VOLTAGE") "150V")
        (field (name "Comment") "StandardResistor")
        (field (name "ADDED BY") "SonerI")
        (field (name "CHECKED BY") "YasinY")
      )
      (libsource (lib "FireANTs_HwLibDB") (part "StandardResistor"))
    )
    (comp (ref "R6")
      (value "StandardResistor")
      (footprint "R_0805_GEN_0.60H")
      (description "RES_STD_4.7K_0.125W_1%_100ppm_0805")
      (fields
        (field (name "TOLERANCE") "1%")
        (field (name "PACKAGE") "0805")
        (field (name "VOLTAGE") "150V")
        (field (name "ADDED BY") "SonerI")
        (field (name "CHECKED BY") "YasinY")
      )
      (libsource (lib "FireANTs_HwLibDB") (part "StandardResistor"))
    )
    (comp (ref "R7")
      (value "10K")
      (footprint "R_0805_GEN_0.70H")
      (description "RES_STD_10K_0.125W_1%_100ppm_0805")
      (fields
        (field (name "TOLERANCE") "1%")
        (field (name "PACKAGE") "0805")
        (field (name "VOLTAGE") "150V")
        (field (name "Comment") "StandardResistor")
        (field (name "ADDED BY") "SonerI")
        (field (name "CHECKED BY") "YasinY")
      )
      (libsource (lib "FireANTs_HwLibDB") (part "StandardResistor"))
    )
    (comp (ref "R8")
      (value "StandardResistor")
      (footprint "R_0805_GEN_0.60H")
      (description "RES_STD_4.7K_0.125W_1%_100ppm_0805")
      (fields
        (field (name "TOLERANCE") "1%")
        (field (name "PACKAGE") "0805")
        (field (name "VOLTAGE") "150V")
        (field (name "ADDED BY") "SonerI")
        (field (name "CHECKED BY") "YasinY")
      )
      (libsource (lib "FireANTs_HwLibDB") (part "StandardResistor"))
    )
    (comp (ref "R9")
      (value "10K")
      (footprint "R_0805_GEN_0.70H")
      (description "RES_STD_10K_0.125W_1%_100ppm_0805")
      (fields
        (field (name "TOLERANCE") "1%")
        (field (name "PACKAGE") "0805")
        (field (name "VOLTAGE") "150V")
        (field (name "Comment") "StandardResistor")
        (field (name "ADDED BY") "SonerI")
        (field (name "CHECKED BY") "YasinY")
      )
      (libsource (lib "FireANTs_HwLibDB") (part "StandardResistor"))
    )
    (comp (ref "R10")
      (value "StandardResistor")
      (footprint "R_0805_GEN_0.60H")
      (description "RES_STD_4.7K_0.125W_1%_100ppm_0805")
      (fields
        (field (name "TOLERANCE") "1%")
        (field (name "PACKAGE") "0805")
        (field (name "VOLTAGE") "150V")
        (field (name "ADDED BY") "SonerI")
        (field (name "CHECKED BY") "YasinY")
      )
      (libsource (lib "FireANTs_HwLibDB") (part "StandardResistor"))
    )
    (comp (ref "R11")
      (value "StandardResistor")
      (footprint "R_0805_GEN_0.60H")
      (description "RES_STD_4.7K_0.125W_1%_100ppm_0805")
      (fields
        (field (name "TOLERANCE") "1%")
        (field (name "PACKAGE") "0805")
        (field (name "VOLTAGE") "150V")
        (field (name "ADDED BY") "SonerI")
        (field (name "CHECKED BY") "YasinY")
      )
      (libsource (lib "FireANTs_HwLibDB") (part "StandardResistor"))
    )
    (comp (ref "R12")
      (value "StandardResistor")
      (footprint "R_0805_GEN_0.60H")
      (description "RES_STD_4.7K_0.125W_1%_100ppm_0805")
      (fields
        (field (name "TOLERANCE") "1%")
        (field (name "PACKAGE") "0805")
        (field (name "VOLTAGE") "150V")
        (field (name "ADDED BY") "SonerI")
        (field (name "CHECKED BY") "YasinY")
      )
      (libsource (lib "FireANTs_HwLibDB") (part "StandardResistor"))
    )
    (comp (ref "R13")
      (value "StandardResistor")
      (footprint "R_0805_GEN_0.60H")
      (description "RES_STD_4.7K_0.125W_1%_100ppm_0805")
      (fields
        (field (name "TOLERANCE") "1%")
        (field (name "PACKAGE") "0805")
        (field (name "VOLTAGE") "150V")
        (field (name "ADDED BY") "SonerI")
        (field (name "CHECKED BY") "YasinY")
      )
      (libsource (lib "FireANTs_HwLibDB") (part "StandardResistor"))
    )
    (comp (ref "R14")
      (value "22R")
      (footprint "R_0805_GEN_0.60H")
      (description "RES_STD_4.7K_0.125W_1%_100ppm_0805")
      (fields
        (field (name "TOLERANCE") "1%")
        (field (name "PACKAGE") "0805")
        (field (name "VOLTAGE") "150V")
        (field (name "ADDED BY") "SonerI")
        (field (name "CHECKED BY") "YasinY")
      )
      (libsource (lib "FireANTs_HwLibDB") (part "StandardResistor"))
    )
    (comp (ref "R15")
      (value "22R")
      (footprint "R_0805_GEN_0.60H")
      (description "RES_STD_4.7K_0.125W_1%_100ppm_0805")
      (fields
        (field (name "TOLERANCE") "1%")
        (field (name "PACKAGE") "0805")
        (field (name "VOLTAGE") "150V")
        (field (name "ADDED BY") "SonerI")
        (field (name "CHECKED BY") "YasinY")
      )
      (libsource (lib "FireANTs_HwLibDB") (part "StandardResistor"))
    )
    (comp (ref "R16")
      (value "10K")
      (footprint "R_0805_GEN_0.70H")
      (description "RES_STD_10K_0.125W_1%_100ppm_0805")
      (fields
        (field (name "TOLERANCE") "1%")
        (field (name "PACKAGE") "0805")
        (field (name "VOLTAGE") "150V")
        (field (name "Comment") "StandardResistor")
        (field (name "ADDED BY") "SonerI")
        (field (name "CHECKED BY") "YasinY")
      )
      (libsource (lib "FireANTs_HwLibDB") (part "StandardResistor"))
    )
    (comp (ref "R17")
      (value "10K")
      (footprint "R_0805_GEN_0.70H")
      (description "RES_STD_10K_0.125W_1%_100ppm_0805")
      (fields
        (field (name "TOLERANCE") "1%")
        (field (name "PACKAGE") "0805")
        (field (name "VOLTAGE") "150V")
        (field (name "Comment") "StandardResistor")
        (field (name "ADDED BY") "SonerI")
        (field (name "CHECKED BY") "YasinY")
      )
      (libsource (lib "FireANTs_HwLibDB") (part "StandardResistor"))
    )
    (comp (ref "R18")
      (value "10K")
      (footprint "R_0805_GEN_0.70H")
      (description "RES_STD_10K_0.125W_1%_100ppm_0805")
      (fields
        (field (name "TOLERANCE") "1%")
        (field (name "PACKAGE") "0805")
        (field (name "VOLTAGE") "150V")
        (field (name "Comment") "StandardResistor")
        (field (name "ADDED BY") "SonerI")
        (field (name "CHECKED BY") "YasinY")
      )
      (libsource (lib "FireANTs_HwLibDB") (part "StandardResistor"))
    )
    (comp (ref "R19")
      (value "10K")
      (footprint "R_0805_GEN_0.70H")
      (description "RES_STD_10K_0.125W_1%_100ppm_0805")
      (fields
        (field (name "TOLERANCE") "1%")
        (field (name "PACKAGE") "0805")
        (field (name "VOLTAGE") "150V")
        (field (name "Comment") "StandardResistor")
        (field (name "ADDED BY") "SonerI")
        (field (name "CHECKED BY") "YasinY")
      )
      (libsource (lib "FireANTs_HwLibDB") (part "StandardResistor"))
    )
    (comp (ref "R20")
      (value "10K")
      (footprint "R_0805_GEN_0.70H")
      (description "RES_STD_10K_0.125W_1%_100ppm_0805")
      (fields
        (field (name "TOLERANCE") "1%")
        (field (name "PACKAGE") "0805")
        (field (name "VOLTAGE") "150V")
        (field (name "Comment") "StandardResistor")
        (field (name "ADDED BY") "SonerI")
        (field (name "CHECKED BY") "YasinY")
      )
      (libsource (lib "FireANTs_HwLibDB") (part "StandardResistor"))
    )
    (comp (ref "R21")
      (value "1.8K")
      (footprint "R_0805_GEN_0.70H")
      (description "RES_STD_442K_0.125W_0.1%_25ppm_0805")
      (fields
        (field (name "TOLERANCE") "0.1%")
        (field (name "PACKAGE") "0805")
        (field (name "SIMILAR PART") "RN73C2A442KBTDF")
        (field (name "VOLTAGE") "100V")
        (field (name "ADDED BY") "İlhanT")
        (field (name "CHECKED BY") "YasinY")
      )
      (libsource (lib "FireANTs_HwLibDB") (part "StandardResistor"))
    )
    (comp (ref "R29")
      (value "StandardJumper")
      (footprint "R_0805_GEN_0.70H")
      (description "RES_STD_0R_0.125W_0805")
      (fields
        (field (name "PACKAGE") "0805")
        (field (name "TOLERANCE") "5%")
        (field (name "VOLTAGE") "150V")
        (field (name "ADDED BY") "İlhanT")
        (field (name "CHECKED BY") "YasinY")
      )
      (libsource (lib "FireANTs_HwLibDB") (part "StandardJumper"))
    )
    (comp (ref "R30")
      (value "10K")
      (footprint "R_0805_GEN_0.70H")
      (description "RES_STD_10K_0.125W_0.01%_5ppm_0805")
      (fields
        (field (name "TOLERANCE") "0.01%")
        (field (name "PACKAGE") "0805")
        (field (name "VOLTAGE") "150V")
        (field (name "Comment") "StandardResistor")
        (field (name "ADDED BY") "HasanA")
        (field (name "CHECKED BY") "YasinY")
      )
      (libsource (lib "FireANTs_HwLibDB") (part "StandardResistor"))
    )
    (comp (ref "R34")
      (value "442K")
      (footprint "R_0805_GEN_0.70H")
      (description "RES_STD_442K_0.125W_0.1%_25ppm_0805")
      (fields
        (field (name "TOLERANCE") "0.1%")
        (field (name "PACKAGE") "0805")
        (field (name "SIMILAR PART") "RN73C2A442KBTDF")
        (field (name "VOLTAGE") "100V")
        (field (name "ADDED BY") "İlhanT")
        (field (name "CHECKED BY") "YasinY")
      )
      (libsource (lib "FireANTs_HwLibDB") (part "StandardResistor"))
    )
    (comp (ref "R36")
      (value "53.6K")
      (footprint "R_0805_GEN_0.70H")
      (description "RES_STD_442K_0.125W_0.1%_25ppm_0805")
      (fields
        (field (name "TOLERANCE") "0.1%")
        (field (name "PACKAGE") "0805")
        (field (name "SIMILAR PART") "RN73C2A442KBTDF")
        (field (name "VOLTAGE") "100V")
        (field (name "ADDED BY") "İlhanT")
        (field (name "CHECKED BY") "YasinY")
      )
      (libsource (lib "FireANTs_HwLibDB") (part "StandardResistor"))
    )
    (comp (ref "R57")
      (value "2.2K")
      (footprint "R_0805_GEN_0.70H")
      (description "RES_STD_2.2K_0.125W_0.05%_10ppm_0805")
      (fields
        (field (name "TOLERANCE") "0.05%")
        (field (name "PACKAGE") "0805")
        (field (name "VOLTAGE") "100V")
        (field (name "Comment") "StandardResistor")
        (field (name "ADDED BY") "İlhanT")
        (field (name "CHECKED BY") "YasinY")
      )
      (libsource (lib "FireANTs_HwLibDB") (part "StandardResistor"))
    )
    (comp (ref "R113")
      (value "10K")
      (footprint "R_0805_GEN_0.70H")
      (description "RES_STD_10K_0.125W_1%_100ppm_0805")
      (fields
        (field (name "TOLERANCE") "1%")
        (field (name "PACKAGE") "0805")
        (field (name "VOLTAGE") "150V")
        (field (name "Comment") "StandardResistor")
        (field (name "ADDED BY") "SonerI")
        (field (name "CHECKED BY") "YasinY")
      )
      (libsource (lib "FireANTs_HwLibDB") (part "StandardResistor"))
    )
    (comp (ref "R114")
      (value "10K")
      (footprint "R_0805_GEN_0.70H")
      (description "RES_STD_10K_0.125W_1%_100ppm_0805")
      (fields
        (field (name "TOLERANCE") "1%")
        (field (name "PACKAGE") "0805")
        (field (name "VOLTAGE") "150V")
        (field (name "Comment") "StandardResistor")
        (field (name "ADDED BY") "SonerI")
        (field (name "CHECKED BY") "YasinY")
      )
      (libsource (lib "FireANTs_HwLibDB") (part "StandardResistor"))
    )
    (comp (ref "R115")
      (value "10K")
      (footprint "R_0805_GEN_0.70H")
      (description "RES_STD_10K_0.125W_1%_100ppm_0805")
      (fields
        (field (name "TOLERANCE") "1%")
        (field (name "PACKAGE") "0805")
        (field (name "VOLTAGE") "150V")
        (field (name "Comment") "StandardResistor")
        (field (name "ADDED BY") "SonerI")
        (field (name "CHECKED BY") "YasinY")
      )
      (libsource (lib "FireANTs_HwLibDB") (part "StandardResistor"))
    )
    (comp (ref "R116")
      (value "10K")
      (footprint "R_0805_GEN_0.70H")
      (description "RES_STD_10K_0.125W_1%_100ppm_0805")
      (fields
        (field (name "TOLERANCE") "1%")
        (field (name "PACKAGE") "0805")
        (field (name "VOLTAGE") "150V")
        (field (name "Comment") "StandardResistor")
        (field (name "ADDED BY") "SonerI")
        (field (name "CHECKED BY") "YasinY")
      )
      (libsource (lib "FireANTs_HwLibDB") (part "StandardResistor"))
    )
    (comp (ref "R117")
      (value "10K")
      (footprint "R_0805_GEN_0.70H")
      (description "RES_STD_10K_0.125W_1%_100ppm_0805")
      (fields
        (field (name "TOLERANCE") "1%")
        (field (name "PACKAGE") "0805")
        (field (name "VOLTAGE") "150V")
        (field (name "Comment") "StandardResistor")
        (field (name "ADDED BY") "SonerI")
        (field (name "CHECKED BY") "YasinY")
      )
      (libsource (lib "FireANTs_HwLibDB") (part "StandardResistor"))
    )
    (comp (ref "R118")
      (value "1.8K")
      (footprint "R_0805_GEN_0.70H")
      (description "RES_STD_442K_0.125W_0.1%_25ppm_0805")
      (fields
        (field (name "TOLERANCE") "0.1%")
        (field (name "PACKAGE") "0805")
        (field (name "SIMILAR PART") "RN73C2A442KBTDF")
        (field (name "VOLTAGE") "100V")
        (field (name "ADDED BY") "İlhanT")
        (field (name "CHECKED BY") "YasinY")
      )
      (libsource (lib "FireANTs_HwLibDB") (part "StandardResistor"))
    )
    (comp (ref "R119")
      (value "16.9K")
      (footprint "R_0805_GEN_0.70H")
      (description "RES_STD_442K_0.125W_0.1%_25ppm_0805")
      (fields
        (field (name "TOLERANCE") "0.1%")
        (field (name "PACKAGE") "0805")
        (field (name "SIMILAR PART") "RN73C2A442KBTDF")
        (field (name "VOLTAGE") "100V")
        (field (name "ADDED BY") "İlhanT")
        (field (name "CHECKED BY") "YasinY")
      )
      (libsource (lib "FireANTs_HwLibDB") (part "StandardResistor"))
    )
    (comp (ref "R120")
      (value "90.9K")
      (footprint "R_0805_GEN_0.70H")
      (description "RES_STD_442K_0.125W_0.1%_25ppm_0805")
      (fields
        (field (name "TOLERANCE") "0.1%")
        (field (name "PACKAGE") "0805")
        (field (name "SIMILAR PART") "RN73C2A442KBTDF")
        (field (name "VOLTAGE") "100V")
        (field (name "ADDED BY") "İlhanT")
        (field (name "CHECKED BY") "YasinY")
      )
      (libsource (lib "FireANTs_HwLibDB") (part "StandardResistor"))
    )
    (comp (ref "R121")
      (value "243K")
      (footprint "R_0805_GEN_0.70H")
      (description "RES_STD_442K_0.125W_0.1%_25ppm_0805")
      (fields
        (field (name "TOLERANCE") "0.1%")
        (field (name "PACKAGE") "0805")
        (field (name "SIMILAR PART") "RN73C2A442KBTDF")
        (field (name "VOLTAGE") "100V")
        (field (name "ADDED BY") "İlhanT")
        (field (name "CHECKED BY") "YasinY")
      )
      (libsource (lib "FireANTs_HwLibDB") (part "StandardResistor"))
    )
    (comp (ref "R122")
      (value "10.2K")
      (footprint "R_0805_GEN_0.70H")
      (description "RES_STD_442K_0.125W_0.1%_25ppm_0805")
      (fields
        (field (name "TOLERANCE") "0.1%")
        (field (name "PACKAGE") "0805")
        (field (name "SIMILAR PART") "RN73C2A442KBTDF")
        (field (name "VOLTAGE") "100V")
        (field (name "ADDED BY") "İlhanT")
        (field (name "CHECKED BY") "YasinY")
      )
      (libsource (lib "FireANTs_HwLibDB") (part "StandardResistor"))
    )
    (comp (ref "R123")
      (value "1K")
      (footprint "R_0805_GEN_0.60H")
      (description "RES_STD_4.7K_0.125W_1%_100ppm_0805")
      (fields
        (field (name "TOLERANCE") "1%")
        (field (name "PACKAGE") "0805")
        (field (name "VOLTAGE") "150V")
        (field (name "ADDED BY") "SonerI")
        (field (name "CHECKED BY") "YasinY")
      )
      (libsource (lib "FireANTs_HwLibDB") (part "StandardResistor"))
    )
    (comp (ref "R126")
      (value "4.7K")
      (footprint "R_0805_GEN_0.60H")
      (description "RES_STD_4.7K_0.125W_1%_100ppm_0805")
      (fields
        (field (name "TOLERANCE") "1%")
        (field (name "PACKAGE") "0805")
        (field (name "VOLTAGE") "150V")
        (field (name "Comment") "StandardResistor")
        (field (name "ADDED BY") "SonerI")
        (field (name "CHECKED BY") "YasinY")
      )
      (libsource (lib "FireANTs_HwLibDB") (part "StandardResistor"))
    )
    (comp (ref "R167")
      (value "2.2K")
      (footprint "R_0805_GEN_0.70H")
      (description "RES_STD_2.2K_0.125W_0.05%_10ppm_0805")
      (fields
        (field (name "TOLERANCE") "0.05%")
        (field (name "PACKAGE") "0805")
        (field (name "VOLTAGE") "100V")
        (field (name "Comment") "StandardResistor")
        (field (name "ADDED BY") "İlhanT")
        (field (name "CHECKED BY") "YasinY")
      )
      (libsource (lib "FireANTs_HwLibDB") (part "StandardResistor"))
    )
    (comp (ref "R169")
      (value "1K")
      (footprint "R_0805_GEN_0.70H")
      (description "RES_STD_1K_0.125W_0.01%_5ppm_0805")
      (fields
        (field (name "TOLERANCE") "0.01%")
        (field (name "PACKAGE") "0805")
        (field (name "SIMILAR PART") "PLTU0805U1001LST5")
        (field (name "VOLTAGE") "150V")
        (field (name "ADDED BY") "HasanA")
        (field (name "CHECKED BY") "YasinY")
      )
      (libsource (lib "FireANTs_HwLibDB") (part "StandardResistor"))
    )
    (comp (ref "R174")
      (value "StandardJumper")
      (footprint "R_0805_GEN_0.70H")
      (description "RES_STD_0R_0.125W_0805")
      (fields
        (field (name "PACKAGE") "0805")
        (field (name "TOLERANCE") "5%")
        (field (name "VOLTAGE") "150V")
        (field (name "ADDED BY") "İlhanT")
        (field (name "CHECKED BY") "YasinY")
      )
      (libsource (lib "FireANTs_HwLibDB") (part "StandardJumper"))
    )
    (comp (ref "R175")
      (value "StandardJumper")
      (footprint "R_0805_GEN_0.70H")
      (description "RES_STD_0R_0.125W_0805")
      (fields
        (field (name "PACKAGE") "0805")
        (field (name "TOLERANCE") "5%")
        (field (name "VOLTAGE") "150V")
        (field (name "ADDED BY") "İlhanT")
        (field (name "CHECKED BY") "YasinY")
      )
      (libsource (lib "FireANTs_HwLibDB") (part "StandardJumper"))
    )
    (comp (ref "R186")
      (value "4.7K")
      (footprint "R_0805_GEN_0.60H")
      (description "RES_STD_4.7K_0.125W_1%_100ppm_0805")
      (fields
        (field (name "TOLERANCE") "1%")
        (field (name "PACKAGE") "0805")
        (field (name "VOLTAGE") "150V")
        (field (name "Comment") "StandardResistor")
        (field (name "ADDED BY") "SonerI")
        (field (name "CHECKED BY") "YasinY")
      )
      (libsource (lib "FireANTs_HwLibDB") (part "StandardResistor"))
    )
    (comp (ref "R191")
      (value "0R")
      (footprint "R_0805_GEN_0.70H")
      (description "RES_STD_0R_0.125W_0805")
      (fields
        (field (name "PACKAGE") "0805")
        (field (name "TOLERANCE") "5%")
        (field (name "VOLTAGE") "150V")
        (field (name "ADDED BY") "İlhanT")
        (field (name "CHECKED BY") "YasinY")
      )
      (libsource (lib "FireANTs_HwLibDB") (part "PlaceHolder"))
    )
    (comp (ref "R192")
      (value "0R")
      (footprint "R_0805_GEN_0.70H")
      (description "RES_STD_0R_0.125W_0805")
      (fields
        (field (name "PACKAGE") "0805")
        (field (name "TOLERANCE") "5%")
        (field (name "VOLTAGE") "150V")
        (field (name "ADDED BY") "İlhanT")
        (field (name "CHECKED BY") "YasinY")
      )
      (libsource (lib "FireANTs_HwLibDB") (part "PlaceHolder"))
    )
    (comp (ref "RLY1")
      (value "G5RL-1A-E-HR-DC24")
      (footprint "relay")
      (description "Electromechanical Relay SPST-NO 16A 24VDC 1.44KOhm Through Hole")
      (fields (field (name "MANUFACTURER") "Omron") (field (name "SUPPLIER PART NUMBER 1") "2213808"))
      (libsource (lib "Printing") (part "G5RL-1A-E-HR-DC24"))
    )
    (comp (ref "SW1")
      (value "L-KLS7-TS4502-6.5-180-T")
      (footprint "L-KLS7-TS4502-6.5-180-T")
      (libsource (lib "Printing") (part "L-KLS7-TS4502-6.5-180-T"))
    )
    (comp (ref "SW2")
      (value "L-KLS7-TS4502-6.5-180-T")
      (footprint "L-KLS7-TS4502-6.5-180-T")
      (libsource (lib "Printing") (part "L-KLS7-TS4502-6.5-180-T"))
    )
    (comp (ref "U10")
      (value "AT24CS64-SSHM-B")
      (footprint "SOIC127P599X175-8N")
      (description "IC EEPROM 64K I2C 1MHZ 8SOIC")
      (libsource (lib "Printing") (part "AT24CS64-SSHM-B"))
    )
    (comp (ref "U11")
      (value "AMS1117-3.3")
      (footprint "SOT229P700X180-4N")
      (description "Sot223/Pkg 1-Amp 3.3-Volt Low Drop Out Voltage Regulatator")
      (fields (field (name "MF") "Advanced Monolithic Systems"))
      (libsource (lib "Printing") (part "AMS1117-3.3"))
    )
    (comp (ref "U15")
      (value "L7812CD2T-TR")
      (footprint "TO254P1515X470-3N")
      (description "Linear Voltage Regulator IC Positive Fixed 1 Output 12V 1.5A D2PAK")
      (fields (field (name "MANUFACTURER") "STMicroelectronics"))
      (libsource (lib "Printing") (part "L7812CD2T-TR"))
    )
    (comp (ref "XTAL1")
      (value "ATS08A-E")
      (footprint "XTAL_HC49P488W43L1085T450H368")
      (description "8MHz Â±30ppm Crystal 20pF 60 Ohms HC-49/US")
      (fields (field (name "MF") "CTS-Frequency Controls"))
      (libsource (lib "Printing") (part "ATS08A-E"))
    )
  )
  (nets
    (net (code "1") (name "+3.3V") (class "Default")
      (node (ref "C1") (pin "1") (pinfunction "1_1") (pintype "passive"))
      (node (ref "C18") (pin "2") (pinfunction "2_2") (pintype "passive"))
      (node (ref "C2") (pin "1") (pinfunction "1_1") (pintype "passive"))
      (node (ref "C3") (pin "1") (pinfunction "1_1") (pintype "passive"))
      (node (ref "C4") (pin "1") (pinfunction "1_1") (pintype "passive"))
      (node (ref "C5") (pin "1") (pinfunction "1_1") (pintype "passive"))
      (node (ref "C6") (pin "1") (pinfunction "1_1") (pintype "passive"))
      (node (ref "C7") (pin "2") (pinfunction "2_2") (pintype "passive"))
      (node (ref "C70") (pin "2") (pinfunction "2_2") (pintype "passive"))
      (node (ref "C71") (pin "2") (pinfunction "2_2") (pintype "passive"))
      (node (ref "IC2") (pin "100") (pinfunction "VDD@6_100") (pintype "bidirectional"))
      (node (ref "IC2") (pin "11") (pinfunction "VDD@1_11") (pintype "bidirectional"))
      (node (ref "IC2") (pin "19") (pinfunction "VDD@2_19") (pintype "bidirectional"))
      (node (ref "IC2") (pin "21") (pinfunction "VREF+_21") (pintype "bidirectional"))
      (node (ref "IC2") (pin "28") (pinfunction "VDD@3_28") (pintype "bidirectional"))
      (node (ref "IC2") (pin "50") (pinfunction "VDD@4_50") (pintype "bidirectional"))
      (node (ref "IC2") (pin "75") (pinfunction "VDD@5_75") (pintype "bidirectional"))
      (node (ref "J3") (pin "2") (pinfunction "2_2") (pintype "passive"))
      (node (ref "J47") (pin "4") (pinfunction "4_4") (pintype "passive"))
      (node (ref "J66") (pin "1") (pinfunction "1_1") (pintype "passive"))
      (node (ref "L1") (pin "1") (pinfunction "1_1") (pintype "passive"))
      (node (ref "Q19") (pin "3") (pinfunction "D_3") (pintype "passive"))
      (node (ref "R1") (pin "2") (pinfunction "2_2") (pintype "passive"))
      (node (ref "R113") (pin "2") (pinfunction "2_2") (pintype "passive"))
      (node (ref "R114") (pin "2") (pinfunction "2_2") (pintype "passive"))
      (node (ref "R115") (pin "2") (pinfunction "2_2") (pintype "passive"))
      (node (ref "R116") (pin "2") (pinfunction "2_2") (pintype "passive"))
      (node (ref "R117") (pin "2") (pinfunction "2_2") (pintype "passive"))
      (node (ref "R118") (pin "1") (pinfunction "1_1") (pintype "passive"))
      (node (ref "R169") (pin "2") (pinfunction "2_2") (pintype "passive"))
      (node (ref "R186") (pin "2") (pinfunction "2_2") (pintype "passive"))
      (node (ref "R2") (pin "2") (pinfunction "2_2") (pintype "passive"))
      (node (ref "R20") (pin "2") (pinfunction "2_2") (pintype "passive"))
      (node (ref "R21") (pin "2") (pinfunction "2_2") (pintype "passive"))
      (node (ref "R7") (pin "1") (pinfunction "1_1") (pintype "passive"))
      (node (ref "SW1") (pin "2") (pinfunction "B0_2") (pintype "passive"))
      (node (ref "SW1") (pin "3") (pinfunction "B1_3") (pintype "passive"))
      (node (ref "U10") (pin "8") (pinfunction "+24V_8") (pintype "power_in"))
      (node (ref "U11") (pin "2") (pinfunction "VOUT_2") (pintype "output"))
      (node (ref "U11") (pin "4") (pinfunction "V0__4") (pintype "passive"))
    )
    (net (code "2") (name "+5V") (class "Default")
      (node (ref "C22") (pin "2") (pinfunction "2_2") (pintype "passive"))
      (node (ref "D1") (pin "2") (pinfunction "A_2") (pintype "passive"))
      (node (ref "D7") (pin "K") (pinfunction "K_K") (pintype "passive"))
      (node (ref "J5") (pin "1") (pinfunction "1_1") (pintype "passive"))
      (node (ref "J58") (pin "1") (pinfunction "1_1") (pintype "passive"))
      (node (ref "J6") (pin "1") (pinfunction "1_1") (pintype "passive"))
      (node (ref "J60") (pin "1") (pinfunction "1_1") (pintype "passive"))
      (node (ref "J62") (pin "1") (pinfunction "1_1") (pintype "passive"))
      (node (ref "J65") (pin "1") (pinfunction "1_1") (pintype "passive"))
      (node (ref "L10") (pin "2") (pinfunction "2_2") (pintype "passive"))
      (node (ref "L3") (pin "1") (pinfunction "1_1") (pintype "passive"))
      (node (ref "L6") (pin "2") (pinfunction "2_2") (pintype "passive"))
      (node (ref "R167") (pin "2") (pinfunction "2_2") (pintype "passive"))
      (node (ref "RLY1") (pin "5") (pinfunction "COIL1_5") (pintype "passive"))
    )
    (net (code "3") (name "+5VD") (class "Default")
      (node (ref "C10") (pin "2") (pinfunction "2_2") (pintype "passive"))
      (node (ref "F1") (pin "1") (pinfunction "1_1") (pintype "passive"))
      (node (ref "L10") (pin "1") (pinfunction "1_1") (pintype "passive"))
      (node (ref "R10") (pin "2") (pinfunction "2_2") (pintype "passive"))
    )
    (net (code "4") (name "+12V") (class "Default")
      (node (ref "C82") (pin "2") (pinfunction "2_2") (pintype "passive"))
      (node (ref "C83") (pin "2") (pinfunction "2_2") (pintype "passive"))
      (node (ref "U15") (pin "2") (pinfunction "OUT_2") (pintype "output"))
    )
    (net (code "5") (name "+24V") (class "Default")
      (node (ref "C20") (pin "1") (pinfunction "1_1") (pintype "passive"))
      (node (ref "C21") (pin "1") (pinfunction "1_1") (pintype "passive"))
      (node (ref "C84") (pin "2") (pinfunction "2_2") (pintype "passive"))
      (node (ref "C85") (pin "2") (pinfunction "2_2") (pintype "passive"))
      (node (ref "D17") (pin "1") (pinfunction "C_1") (pintype "passive"))
      (node (ref "D8") (pin "1") (pinfunction "C_1") (pintype "passive"))
      (node (ref "L4") (pin "1") (pinfunction "1_1") (pintype "passive"))
      (node (ref "U15") (pin "1") (pinfunction "IN_1") (pintype "input"))
    )
    (net (code "6") (name "+24VA") (class "Default")
      (node (ref "J20") (pin "1") (pinfunction "1_1") (pintype "passive"))
      (node (ref "J20") (pin "2") (pinfunction "2_2") (pintype "passive"))
      (node (ref "J20") (pin "3") (pinfunction "3_3") (pintype "passive"))
      (node (ref "J20") (pin "4") (pinfunction "4_4") (pintype "passive"))
      (node (ref "J20") (pin "5") (pinfunction "5_5") (pintype "passive"))
      (node (ref "J63") (pin "1") (pinfunction "1_1") (pintype "passive"))
      (node (ref "J64") (pin "1") (pinfunction "1_1") (pintype "passive"))
      (node (ref "J7") (pin "1") (pinfunction "1_1") (pintype "passive"))
      (node (ref "J8") (pin "1") (pinfunction "1_1") (pintype "passive"))
      (node (ref "R30") (pin "2") (pinfunction "2_2") (pintype "passive"))
      (node (ref "RLY1") (pin "1") (pinfunction "COM_1") (pintype "passive"))
    )
    (net (code "7") (name "/4") (class "Default")
      (node (ref "IC2") (pin "17") (pinfunction "PC2_17") (pintype "bidirectional"))
      (node (ref "J58") (pin "3") (pinfunction "3_3") (pintype "passive"))
    )
    (net (code "8") (name "/12V_MOTOR") (class "Default")
      (node (ref "IC2") (pin "64") (pinfunction "PC7_64") (pintype "bidirectional"))
    )
    (net (code "9") (name "/24V_SW") (class "Default")
      (node (ref "Fuse1") (pin "1") (pinfunction "1_1") (pintype "passive"))
      (node (ref "J10") (pin "1") (pinfunction "1_1") (pintype "passive"))
      (node (ref "RLY1") (pin "3") (pinfunction "NO_3") (pintype "passive"))
    )
    (net (code "10") (name "/BOOT0") (class "Default")
      (node (ref "IC2") (pin "94") (pinfunction "BOOT0_94") (pintype "bidirectional"))
      (node (ref "R19") (pin "2") (pinfunction "2_2") (pintype "passive"))
      (node (ref "SW1") (pin "1") (pinfunction "A0_1") (pintype "passive"))
      (node (ref "SW1") (pin "4") (pinfunction "A1_4") (pintype "passive"))
    )
    (net (code "11") (name "/BTN_EN1") (class "Default")
      (node (ref "IC2") (pin "33") (pinfunction "PC4_33") (pintype "bidirectional"))
    )
    (net (code "12") (name "/BTN_EN2") (class "Default")
      (node (ref "IC2") (pin "34") (pinfunction "PC5_34") (pintype "bidirectional"))
    )
    (net (code "13") (name "/Cam") (class "Default")
      (node (ref "IC2") (pin "18") (pinfunction "PC3_18") (pintype "bidirectional"))
    )
    (net (code "14") (name "/E0_DIR") (class "Default")
      (node (ref "IC2") (pin "84") (pinfunction "PD3_84") (pintype "bidirectional"))
    )
    (net (code "15") (name "/E0_EN") (class "Default")
      (node (ref "IC2") (pin "89") (pinfunction "PB3_89") (pintype "bidirectional"))
    )
    (net (code "16") (name "/E0_STEP") (class "Default")
      (node (ref "IC2") (pin "87") (pinfunction "PD6_87") (pintype "bidirectional"))
    )
    (net (code "17") (name "/E0_UART") (class "Default")
      (node (ref "IC2") (pin "56") (pinfunction "PD9_56") (pintype "bidirectional"))
    )
    (net (code "18") (name "/E1-") (class "Default")
      (node (ref "IC2") (pin "38") (pinfunction "PE7_38") (pintype "bidirectional"))
    )
    (net (code "19") (name "/E1_DIR") (class "Default")
      (node (ref "IC2") (pin "24") (pinfunction "PA1_24") (pintype "bidirectional"))
    )
    (net (code "20") (name "/E1_EN") (class "Default")
      (node (ref "IC2") (pin "26") (pinfunction "PA3_26") (pintype "bidirectional"))
    )
    (net (code "21") (name "/E1_STEP") (class "Default")
      (node (ref "IC2") (pin "62") (pinfunction "PD15_62") (pintype "bidirectional"))
    )
    (net (code "22") (name "/E1_UART") (class "Default")
      (node (ref "IC2") (pin "55") (pinfunction "PD8_55") (pintype "bidirectional"))
    )
    (net (code "23") (name "/ESP_EN") (class "Default")
      (node (ref "IC2") (pin "40") (pinfunction "PE9_40") (pintype "bidirectional"))
    )
    (net (code "24") (name "/FAN1") (class "Default")
      (node (ref "IC2") (pin "8") (pinfunction "PC14_8") (pintype "bidirectional"))
      (node (ref "J20") (pin "7") (pinfunction "7_7") (pintype "passive"))
    )
    (net (code "25") (name "/FAN2") (class "Default")
      (node (ref "IC2") (pin "36") (pinfunction "PB1_36") (pintype "bidirectional"))
      (node (ref "J20") (pin "8") (pinfunction "8_8") (pintype "passive"))
    )
    (net (code "26") (name "/HEATER") (class "Default")
      (node (ref "IC2") (pin "4") (pinfunction "PE5_4") (pintype "bidirectional"))
    )
    (net (code "27") (name "/HEATER2") (class "Default")
      (node (ref "IC2") (pin "35") (pinfunction "PB0_35") (pintype "bidirectional"))
    )
    (net (code "28") (name "/HOTBED") (class "Default")
      (node (ref "IC2") (pin "23") (pinfunction "PA0_23") (pintype "bidirectional"))
    )
    (net (code "29") (name "/HOTEND") (class "Default")
      (node (ref "J20") (pin "11") (pinfunction "11_11") (pintype "passive"))
      (node (ref "J20") (pin "12") (pinfunction "12_12") (pintype "passive"))
      (node (ref "J20") (pin "13") (pinfunction "13_13") (pintype "passive"))
      (node (ref "J20") (pin "14") (pinfunction "14_14") (pintype "passive"))
    )
    (net (code "30") (name "/I2C_SCL") (class "Default")
      (node (ref "IC2") (pin "92") (pinfunction "PB6_92") (pintype "bidirectional"))
      (node (ref "R2") (pin "1") (pinfunction "1_1") (pintype "passive"))
      (node (ref "U10") (pin "6") (pinfunction "SCL_6") (pintype "input"))
    )
    (net (code "31") (name "/I2C_SDA") (class "Default")
      (node (ref "IC2") (pin "93") (pinfunction "PB7_93") (pintype "bidirectional"))
      (node (ref "R1") (pin "1") (pinfunction "1_1") (pintype "passive"))
      (node (ref "U10") (pin "5") (pinfunction "SDA_5") (pintype "bidirectional"))
    )
    (net (code "32") (name "/IN22") (class "Default")
      (node (ref "IC2") (pin "52") (pinfunction "PB13_52") (pintype "bidirectional"))
    )
    (net (code "33") (name "/LED") (class "Default")
      (node (ref "IC2") (pin "9") (pinfunction "PC15_9") (pintype "bidirectional"))
    )
    (net (code "34") (name "/MOS_1") (class "Default")
      (node (ref "IC2") (pin "63") (pinfunction "PC6_63") (pintype "bidirectional"))
    )
    (net (code "35") (name "/MOS_2") (class "Default")
      (node (ref "IC2") (pin "58") (pinfunction "PD11_58") (pintype "bidirectional"))
    )
    (net (code "36") (name "/MOS_3") (class "Default")
      (node (ref "IC2") (pin "57") (pinfunction "PD10_57") (pintype "bidirectional"))
    )
    (net (code "37") (name "/MOS_4") (class "Default")
      (node (ref "IC2") (pin "46") (pinfunction "PE15_46") (pintype "bidirectional"))
    )
    (net (code "38") (name "/MOS_5") (class "Default")
      (node (ref "IC2") (pin "44") (pinfunction "PE13_44") (pintype "bidirectional"))
    )
    (net (code "39") (name "/MOS_6") (class "Default")
      (node (ref "IC2") (pin "43") (pinfunction "PE12_43") (pintype "bidirectional"))
    )
    (net (code "40") (name "/MOS_7") (class "Default")
      (node (ref "IC2") (pin "41") (pinfunction "PE10_41") (pintype "bidirectional"))
    )
    (net (code "41") (name "/MOS_8") (class "Default")
      (node (ref "IC2") (pin "39") (pinfunction "PE8_39") (pintype "bidirectional"))
    )
    (net (code "42") (name "/MOS_9") (class "Default")
      (node (ref "IC2") (pin "60") (pinfunction "PD13_60") (pintype "bidirectional"))
    )
    (net (code "43") (name "/MT_DET1") (class "Default")
      (node (ref "IC2") (pin "29") (pinfunction "PA4_29") (pintype "bidirectional"))
    )
    (net (code "44") (name "/MT_DET2") (class "Default")
      (node (ref "IC2") (pin "5") (pinfunction "PE6_5") (pintype "bidirectional"))
    )
    (net (code "45") (name "/ON_OFF") (class "Default")
      (node (ref "IC2") (pin "42") (pinfunction "PE11_42") (pintype "bidirectional"))
      (node (ref "R123") (pin "1") (pinfunction "1_1") (pintype "passive"))
      (node (ref "R126") (pin "1") (pinfunction "1_1") (pintype "passive"))
    )
    (net (code "46") (name "/OSC_IN") (class "Default")
      (node (ref "C8") (pin "2") (pinfunction "2_2") (pintype "passive"))
      (node (ref "IC2") (pin "12") (pinfunction "PH0_12") (pintype "bidirectional"))
      (node (ref "XTAL1") (pin "1") (pinfunction "1_1") (pintype "passive"))
    )
    (net (code "47") (name "/OSC_OUT") (class "Default")
      (node (ref "C9") (pin "2") (pinfunction "2_2") (pintype "passive"))
      (node (ref "IC2") (pin "13") (pinfunction "PH1_13") (pintype "bidirectional"))
      (node (ref "XTAL1") (pin "2") (pinfunction "2_2") (pintype "passive"))
    )
    (net (code "48") (name "/PA5") (class "Default")
      (node (ref "IC2") (pin "30") (pinfunction "PA5_30") (pintype "bidirectional"))
    )
    (net (code "49") (name "/PA6") (class "Default")
      (node (ref "IC2") (pin "31") (pinfunction "PA6_31") (pintype "bidirectional"))
    )
    (net (code "50") (name "/PA8") (class "Default")
      (node (ref "IC2") (pin "67") (pinfunction "PA8_67") (pintype "bidirectional"))
    )
    (net (code "51") (name "/RESET") (class "Default")
      (node (ref "C16") (pin "2") (pinfunction "2_2") (pintype "passive"))
      (node (ref "IC2") (pin "14") (pinfunction "NRST_14") (pintype "bidirectional"))
      (node (ref "J3") (pin "5") (pinfunction "5_5") (pintype "passive"))
      (node (ref "R20") (pin "1") (pinfunction "1_1") (pintype "passive"))
      (node (ref "SW2") (pin "2") (pinfunction "B0_2") (pintype "passive"))
      (node (ref "SW2") (pin "3") (pinfunction "B1_3") (pintype "passive"))
    )
    (net (code "52") (name "/RXD0") (class "Default")
      (node (ref "IC2") (pin "69") (pinfunction "PA10_69") (pintype "bidirectional"))
      (node (ref "J6") (pin "3") (pinfunction "3_3") (pintype "passive"))
    )
    (net (code "53") (name "/RXD3") (class "Default")
      (node (ref "IC2") (pin "48") (pinfunction "PB11_48") (pintype "bidirectional"))
      (node (ref "J5") (pin "4") (pinfunction "4_4") (pintype "passive"))
    )
    (net (code "54") (name "/SD_DET") (class "Default")
      (node (ref "D6") (pin "K") (pinfunction "C_K") (pintype "passive"))
      (node (ref "IC2") (pin "59") (pinfunction "PD12_59") (pintype "bidirectional"))
      (node (ref "J47") (pin "9") (pinfunction "9_9") (pintype "passive"))
      (node (ref "R113") (pin "1") (pinfunction "1_1") (pintype "passive"))
    )
    (net (code "55") (name "/SPI1_MOSI") (class "Default")
      (node (ref "IC2") (pin "32") (pinfunction "PA7_32") (pintype "bidirectional"))
      (node (ref "J60") (pin "3") (pinfunction "3_3") (pintype "passive"))
    )
    (net (code "56") (name "/SPI3_CS") (class "Default")
      (node (ref "R117") (pin "1") (pinfunction "1_1") (pintype "passive"))
      (node (ref "R174") (pin "2") (pinfunction "2_2") (pintype "passive"))
      (node (ref "R175") (pin "1") (pinfunction "1_1") (pintype "passive"))
      (node (ref "R186") (pin "1") (pinfunction "1_1") (pintype "passive"))
    )
    (net (code "57") (name "/SPI3_MISO") (class "Default")
      (node (ref "IC2") (pin "79") (pinfunction "PC11_79") (pintype "bidirectional"))
      (node (ref "J47") (pin "7") (pinfunction "7_7") (pintype "passive"))
      (node (ref "R114") (pin "1") (pinfunction "1_1") (pintype "passive"))
    )
    (net (code "58") (name "/SPI3_MOSI") (class "Default")
      (node (ref "IC2") (pin "80") (pinfunction "PC12_80") (pintype "bidirectional"))
      (node (ref "J47") (pin "3") (pinfunction "3_3") (pintype "passive"))
      (node (ref "R116") (pin "1") (pinfunction "1_1") (pintype "passive"))
    )
    (net (code "59") (name "/SPI3_SCK") (class "Default")
      (node (ref "IC2") (pin "78") (pinfunction "PC10_78") (pintype "bidirectional"))
      (node (ref "J47") (pin "5") (pinfunction "5_5") (pintype "passive"))
      (node (ref "R115") (pin "1") (pinfunction "1_1") (pintype "passive"))
    )
    (net (code "60") (name "/SSR_2") (class "Default")
      (node (ref "IC2") (pin "45") (pinfunction "PE14_45") (pintype "bidirectional"))
    )
    (net (code "61") (name "/SW_CLK") (class "Default")
      (node (ref "IC2") (pin "76") (pinfunction "PA14_76") (pintype "bidirectional"))
      (node (ref "J3") (pin "3") (pinfunction "3_3") (pintype "passive"))
      (node (ref "R4") (pin "1") (pinfunction "1_1") (pintype "passive"))
      (node (ref "R9") (pin "2") (pinfunction "2_2") (pintype "passive"))
    )
    (net (code "62") (name "/SW_DIO") (class "Default")
      (node (ref "IC2") (pin "72") (pinfunction "PA13_72") (pintype "bidirectional"))
      (node (ref "J3") (pin "1") (pinfunction "1_1") (pintype "passive"))
      (node (ref "R7") (pin "2") (pinfunction "2_2") (pintype "passive"))
    )
    (net (code "63") (name "/TB") (class "Default")
      (node (ref "IC2") (pin "15") (pinfunction "PC0_15") (pintype "bidirectional"))
    )
    (net (code "64") (name "/TH1") (class "Default")
      (node (ref "IC2") (pin "16") (pinfunction "PC1_16") (pintype "bidirectional"))
      (node (ref "J20") (pin "6") (pinfunction "6_6") (pintype "passive"))
    )
    (net (code "65") (name "/TH2") (class "Default")
      (node (ref "IC2") (pin "25") (pinfunction "PA2_25") (pintype "bidirectional"))
    )
    (net (code "66") (name "/TMC_MISO") (class "Default")
      (node (ref "IC2") (pin "82") (pinfunction "PD1_82") (pintype "bidirectional"))
      (node (ref "J66") (pin "2") (pinfunction "2_2") (pintype "passive"))
      (node (ref "R57") (pin "2") (pinfunction "2_2") (pintype "passive"))
    )
    (net (code "67") (name "/TMC_MOSI") (class "Default")
      (node (ref "IC2") (pin "61") (pinfunction "PD14_61") (pintype "bidirectional"))
      (node (ref "J62") (pin "3") (pinfunction "3_3") (pintype "passive"))
    )
    (net (code "68") (name "/TMC_SCLK") (class "Default")
      (node (ref "IC2") (pin "81") (pinfunction "PD0_81") (pintype "bidirectional"))
      (node (ref "J65") (pin "3") (pinfunction "3_3") (pintype "passive"))
    )
    (net (code "69") (name "/TXD0") (class "Default")
      (node (ref "IC2") (pin "68") (pinfunction "PA9_68") (pintype "bidirectional"))
      (node (ref "J6") (pin "4") (pinfunction "4_4") (pintype "passive"))
    )
    (net (code "70") (name "/TXD3") (class "Default")
      (node (ref "IC2") (pin "47") (pinfunction "PB10_47") (pintype "bidirectional"))
      (node (ref "J5") (pin "3") (pinfunction "3_3") (pintype "passive"))
    )
    (net (code "71") (name "/USB1_CPU_N") (class "Default")
      (node (ref "IC2") (pin "53") (pinfunction "PB14_53") (pintype "bidirectional"))
      (node (ref "R15") (pin "1") (pinfunction "1_1") (pintype "passive"))
    )
    (net (code "72") (name "/USB1_CPU_P") (class "Default")
      (node (ref "IC2") (pin "54") (pinfunction "PB15_54") (pintype "bidirectional"))
      (node (ref "R14") (pin "1") (pinfunction "1_1") (pintype "passive"))
    )
    (net (code "73") (name "/USB1_N") (class "Default")
      (node (ref "J4") (pin "03") (pinfunction "D+_03") (pintype "bidirectional"))
      (node (ref "R15") (pin "2") (pinfunction "2_2") (pintype "passive"))
      (node (ref "R16") (pin "2") (pinfunction "2_2") (pintype "passive"))
    )
    (net (code "74") (name "/USB1_P") (class "Default")
      (node (ref "J4") (pin "02") (pinfunction "D-_02") (pintype "bidirectional"))
      (node (ref "R14") (pin "2") (pinfunction "2_2") (pintype "passive"))
      (node (ref "R17") (pin "2") (pinfunction "2_2") (pintype "passive"))
    )
    (net (code "75") (name "/USB2_N") (class "Default")
      (node (ref "J2") (pin "3") (pinfunction "D+_3") (pintype "bidirectional"))
      (node (ref "R11") (pin "2") (pinfunction "2_2") (pintype "passive"))
      (node (ref "R8") (pin "2") (pinfunction "2_2") (pintype "passive"))
    )
    (net (code "76") (name "/USB2_P") (class "Default")
      (node (ref "J2") (pin "2") (pinfunction "D-_2") (pintype "bidirectional"))
      (node (ref "R12") (pin "2") (pinfunction "2_2") (pintype "passive"))
      (node (ref "R6") (pin "2") (pinfunction "2_2") (pintype "passive"))
    )
    (net (code "77") (name "/USB_CPU_N") (class "Default")
      (node (ref "C11") (pin "2") (pinfunction "2_2") (pintype "passive"))
      (node (ref "IC2") (pin "70") (pinfunction "PA11_70") (pintype "bidirectional"))
      (node (ref "R8") (pin "1") (pinfunction "1_1") (pintype "passive"))
    )
    (net (code "78") (name "/USB_CPU_P") (class "Default")
      (node (ref "C12") (pin "2") (pinfunction "2_2") (pintype "passive"))
      (node (ref "IC2") (pin "71") (pinfunction "PA12_71") (pintype "bidirectional"))
      (node (ref "R5") (pin "1") (pinfunction "1_1") (pintype "passive"))
      (node (ref "R6") (pin "1") (pinfunction "1_1") (pintype "passive"))
    )
    (net (code "79") (name "/VCAP1") (class "Default")
      (node (ref "C15") (pin "2") (pinfunction "2_2") (pintype "passive"))
      (node (ref "C80") (pin "2") (pinfunction "2_2") (pintype "passive"))
      (node (ref "IC2") (pin "49") (pinfunction "VCAP_1_49") (pintype "bidirectional"))
    )
    (net (code "80") (name "/VCAP2") (class "Default")
      (node (ref "C14") (pin "2") (pinfunction "2_2") (pintype "passive"))
      (node (ref "C79") (pin "2") (pinfunction "2_2") (pintype "passive"))
      (node (ref "IC2") (pin "73") (pinfunction "VCAP_2_73") (pintype "bidirectional"))
    )
    (net (code "81") (name "/WIFI_IO0") (class "Default")
      (node (ref "IC2") (pin "7") (pinfunction "PC13_7") (pintype "bidirectional"))
    )
    (net (code "82") (name "/X-") (class "Default")
      (node (ref "IC2") (pin "77") (pinfunction "PA15_77") (pintype "bidirectional"))
    )
    (net (code "83") (name "/X_DIR") (class "Default")
      (node (ref "IC2") (pin "1") (pinfunction "PE2_1") (pintype "bidirectional"))
    )
    (net (code "84") (name "/X_EN") (class "Default")
      (node (ref "IC2") (pin "3") (pinfunction "PE4_3") (pintype "bidirectional"))
    )
    (net (code "85") (name "/X_STEP") (class "Default")
      (node (ref "IC2") (pin "2") (pinfunction "PE3_2") (pintype "bidirectional"))
    )
    (net (code "86") (name "/X_UART") (class "Default")
      (node (ref "IC2") (pin "86") (pinfunction "PD5_86") (pintype "bidirectional"))
    )
    (net (code "87") (name "/Y-") (class "Default")
      (node (ref "IC2") (pin "83") (pinfunction "PD2_83") (pintype "bidirectional"))
    )
    (net (code "88") (name "/Y_DIR") (class "Default")
      (node (ref "IC2") (pin "96") (pinfunction "PB9_96") (pintype "bidirectional"))
    )
    (net (code "89") (name "/Y_EN") (class "Default")
      (node (ref "IC2") (pin "98") (pinfunction "PE1_98") (pintype "bidirectional"))
    )
    (net (code "90") (name "/Y_STEP") (class "Default")
      (node (ref "IC2") (pin "97") (pinfunction "PE0_97") (pintype "bidirectional"))
    )
    (net (code "91") (name "/Y_UART") (class "Default")
      (node (ref "IC2") (pin "88") (pinfunction "PD7_88") (pintype "bidirectional"))
    )
    (net (code "92") (name "/Z-") (class "Default")
      (node (ref "IC2") (pin "65") (pinfunction "PC8_65") (pintype "bidirectional"))
    )
    (net (code "93") (name "/Z_0") (class "Default")
      (node (ref "J20") (pin "9") (pinfunction "9_9") (pintype "passive"))
    )
    (net (code "94") (name "/Z_DIR") (class "Default")
      (node (ref "IC2") (pin "90") (pinfunction "PB4_90") (pintype "bidirectional"))
    )
    (net (code "95") (name "/Z_EN") (class "Default")
      (node (ref "IC2") (pin "95") (pinfunction "PB8_95") (pintype "bidirectional"))
    )
    (net (code "96") (name "/Z_STEP") (class "Default")
      (node (ref "IC2") (pin "91") (pinfunction "PB5_91") (pintype "bidirectional"))
    )
    (net (code "97") (name "/Z_UART") (class "Default")
      (node (ref "IC2") (pin "85") (pinfunction "PD4_85") (pintype "bidirectional"))
    )
    (net (code "98") (name "GND") (class "Default")
      (node (ref "C1") (pin "2") (pinfunction "2_2") (pintype "passive"))
      (node (ref "C10") (pin "1") (pinfunction "1_1") (pintype "passive"))
      (node (ref "C13") (pin "1") (pinfunction "1_1") (pintype "passive"))
      (node (ref "C14") (pin "1") (pinfunction "1_1") (pintype "passive"))
      (node (ref "C15") (pin "1") (pinfunction "1_1") (pintype "passive"))
      (node (ref "C16") (pin "1") (pinfunction "1_1") (pintype "passive"))
      (node (ref "C18") (pin "1") (pinfunction "1_1") (pintype "passive"))
      (node (ref "C19") (pin "1") (pinfunction "1_1") (pintype "passive"))
      (node (ref "C2") (pin "2") (pinfunction "2_2") (pintype "passive"))
      (node (ref "C20") (pin "2") (pinfunction "2_2") (pintype "passive"))
      (node (ref "C21") (pin "2") (pinfunction "2_2") (pintype "passive"))
      (node (ref "C22") (pin "1") (pinfunction "1_1") (pintype "passive"))
      (node (ref "C27") (pin "1") (pinfunction "1_1") (pintype "passive"))
      (node (ref "C3") (pin "2") (pinfunction "2_2") (pintype "passive"))
      (node (ref "C37") (pin "1") (pinfunction "1_1") (pintype "passive"))
      (node (ref "C4") (pin "2") (pinfunction "2_2") (pintype "passive"))
      (node (ref "C5") (pin "2") (pinfunction "2_2") (pintype "passive"))
      (node (ref "C6") (pin "2") (pinfunction "2_2") (pintype "passive"))
      (node (ref "C64") (pin "1") (pinfunction "1_1") (pintype "passive"))
      (node (ref "C7") (pin "1") (pinfunction "1_1") (pintype "passive"))
      (node (ref "C70") (pin "1") (pinfunction "1_1") (pintype "passive"))
      (node (ref "C71") (pin "1") (pinfunction "1_1") (pintype "passive"))
      (node (ref "C72") (pin "1") (pinfunction "1_1") (pintype "passive"))
      (node (ref "C73") (pin "1") (pinfunction "1_1") (pintype "passive"))
      (node (ref "C74") (pin "1") (pinfunction "1_1") (pintype "passive"))
      (node (ref "C75") (pin "1") (pinfunction "1_1") (pintype "passive"))
      (node (ref "C77") (pin "1") (pinfunction "1_1") (pintype "passive"))
      (node (ref "C79") (pin "1") (pinfunction "1_1") (pintype "passive"))
      (node (ref "C8") (pin "1") (pinfunction "1_1") (pintype "passive"))
      (node (ref "C80") (pin "1") (pinfunction "1_1") (pintype "passive"))
      (node (ref "C82") (pin "1") (pinfunction "1_1") (pintype "passive"))
      (node (ref "C83") (pin "1") (pinfunction "1_1") (pintype "passive"))
      (node (ref "C84") (pin "1") (pinfunction "1_1") (pintype "passive"))
      (node (ref "C85") (pin "1") (pinfunction "1_1") (pintype "passive"))
      (node (ref "C9") (pin "1") (pinfunction "1_1") (pintype "passive"))
      (node (ref "C94") (pin "1") (pinfunction "1_1") (pintype "passive"))
      (node (ref "D14") (pin "K") (pinfunction "C_K") (pintype "passive"))
      (node (ref "D15") (pin "K") (pinfunction "C_K") (pintype "passive"))
      (node (ref "D16") (pin "K") (pinfunction "C_K") (pintype "passive"))
      (node (ref "D2") (pin "A") (pinfunction "A_A") (pintype "passive"))
      (node (ref "D3") (pin "K") (pinfunction "C_K") (pintype "passive"))
      (node (ref "IC2") (pin "10") (pinfunction "VSS@1_10") (pintype "bidirectional"))
      (node (ref "IC2") (pin "20") (pinfunction "VSSA_20") (pintype "bidirectional"))
      (node (ref "IC2") (pin "27") (pinfunction "VSS@2_27") (pintype "bidirectional"))
      (node (ref "IC2") (pin "74") (pinfunction "VSS@3_74") (pintype "bidirectional"))
      (node (ref "IC2") (pin "99") (pinfunction "VSS@4_99") (pintype "bidirectional"))
      (node (ref "IC3") (pin "7") (pinfunction "GND_7") (pintype "power_in"))
      (node (ref "IC3") (pin "9") (pinfunction "PAD_9") (pintype "bidirectional"))
      (node (ref "J10") (pin "2") (pinfunction "2_2") (pintype "passive"))
      (node (ref "J2") (pin "4") (pinfunction "GND_4") (pintype "power_in"))
      (node (ref "J2") (pin "S1") (pinfunction "SHIELD_S1") (pintype "passive"))
      (node (ref "J2") (pin "S2") (pinfunction "SHIELD_S2") (pintype "passive"))
      (node (ref "J20") (pin "15") (pinfunction "15_15") (pintype "passive"))
      (node (ref "J20") (pin "16") (pinfunction "16_16") (pintype "passive"))
      (node (ref "J3") (pin "4") (pinfunction "4_4") (pintype "passive"))
      (node (ref "J3") (pin "6") (pinfunction "6_6") (pintype "passive"))
      (node (ref "J4") (pin "04") (pinfunction "GND_04") (pintype "power_in"))
      (node (ref "J4") (pin "S1") (pinfunction "SHIELD_S1") (pintype "passive"))
      (node (ref "J4") (pin "S2") (pinfunction "SHIELD_S2") (pintype "passive"))
      (node (ref "J47") (pin "10") (pinfunction "10_10") (pintype "passive"))
      (node (ref "J47") (pin "6") (pinfunction "6_6") (pintype "passive"))
      (node (ref "J5") (pin "2") (pinfunction "2_2") (pintype "passive"))
      (node (ref "J58") (pin "2") (pinfunction "2_2") (pintype "passive"))
      (node (ref "J6") (pin "2") (pinfunction "2_2") (pintype "passive"))
      (node (ref "J60") (pin "2") (pinfunction "2_2") (pintype "passive"))
      (node (ref "J62") (pin "2") (pinfunction "2_2") (pintype "passive"))
      (node (ref "J63") (pin "2") (pinfunction "2_2") (pintype "passive"))
      (node (ref "J64") (pin "2") (pinfunction "2_2") (pintype "passive"))
      (node (ref "J65") (pin "2") (pinfunction "2_2") (pintype "passive"))
      (node (ref "J7") (pin "2") (pinfunction "2_2") (pintype "passive"))
      (node (ref "J8") (pin "2") (pinfunction "2_2") (pintype "passive"))
      (node (ref "L2") (pin "1") (pinfunction "1_1") (pintype "passive"))
      (node (ref "Q6") (pin "3") (pinfunction "SOURCE_3") (pintype "passive"))
      (node (ref "Q7") (pin "2") (pinfunction "E_2") (pintype "passive"))
      (node (ref "R120") (pin "1") (pinfunction "1_1") (pintype "passive"))
      (node (ref "R121") (pin "1") (pinfunction "1_1") (pintype "passive"))
      (node (ref "R122") (pin "1") (pinfunction "1_1") (pintype "passive"))
      (node (ref "R126") (pin "2") (pinfunction "2_2") (pintype "passive"))
      (node (ref "R16") (pin "1") (pinfunction "1_1") (pintype "passive"))
      (node (ref "R17") (pin "1") (pinfunction "1_1") (pintype "passive"))
      (node (ref "R18") (pin "1") (pinfunction "1_1") (pintype "passive"))
      (node (ref "R19") (pin "1") (pinfunction "1_1") (pintype "passive"))
      (node (ref "R192") (pin "1") (pinfunction "1_1") (pintype "passive"))
      (node (ref "R29") (pin "2") (pinfunction "2_2") (pintype "passive"))
      (node (ref "R3") (pin "2") (pinfunction "2_2") (pintype "passive"))
      (node (ref "R57") (pin "1") (pinfunction "1_1") (pintype "passive"))
      (node (ref "R9") (pin "1") (pinfunction "1_1") (pintype "passive"))
      (node (ref "SW2") (pin "1") (pinfunction "A0_1") (pintype "passive"))
      (node (ref "SW2") (pin "4") (pinfunction "A1_4") (pintype "passive"))
      (node (ref "U10") (pin "1") (pinfunction "A0_1") (pintype "input"))
      (node (ref "U10") (pin "2") (pinfunction "A1_2") (pintype "input"))
      (node (ref "U10") (pin "3") (pinfunction "A2_3") (pintype "input"))
      (node (ref "U10") (pin "4") (pinfunction "GND_4") (pintype "power_in"))
      (node (ref "U10") (pin "7") (pinfunction "WP_7") (pintype "input"))
      (node (ref "U11") (pin "1") (pinfunction "ADJ/GND_1") (pintype "power_in"))
      (node (ref "U15") (pin "3") (pinfunction "GND_3") (pintype "power_in"))
    )
    (net (code "99") (name "Net-(C11-Pad1)") (class "Default")
      (node (ref "C11") (pin "1") (pinfunction "1_1") (pintype "passive"))
      (node (ref "C12") (pin "1") (pinfunction "1_1") (pintype "passive"))
      (node (ref "R10") (pin "1") (pinfunction "1_1") (pintype "passive"))
      (node (ref "R11") (pin "1") (pinfunction "1_1") (pintype "passive"))
      (node (ref "R12") (pin "1") (pinfunction "1_1") (pintype "passive"))
      (node (ref "R13") (pin "2") (pinfunction "2_2") (pintype "passive"))
    )
    (net (code "100") (name "Net-(C17-Pad1)") (class "Default")
      (node (ref "C17") (pin "1") (pinfunction "1_1") (pintype "passive"))
      (node (ref "R191") (pin "2") (pinfunction "2_2") (pintype "passive"))
    )
    (net (code "101") (name "Net-(C64-Pad2)") (class "Default")
      (node (ref "C64") (pin "2") (pinfunction "2_2") (pintype "passive"))
      (node (ref "C72") (pin "2") (pinfunction "2_2") (pintype "passive"))
      (node (ref "C73") (pin "2") (pinfunction "2_2") (pintype "passive"))
      (node (ref "L5") (pin "2") (pinfunction "2_2") (pintype "passive"))
      (node (ref "L6") (pin "1") (pinfunction "1_1") (pintype "passive"))
      (node (ref "R36") (pin "2") (pinfunction "2_2") (pintype "passive"))
    )
    (net (code "102") (name "Net-(C75-Pad2)") (class "Default")
      (node (ref "C75") (pin "2") (pinfunction "2_2") (pintype "passive"))
      (node (ref "R119") (pin "1") (pinfunction "1_1") (pintype "passive"))
    )
    (net (code "103") (name "Net-(C93-Pad2)") (class "Default")
      (node (ref "C93") (pin "2") (pinfunction "2_2") (pintype "passive"))
      (node (ref "R192") (pin "2") (pinfunction "2_2") (pintype "passive"))
    )
    (net (code "104") (name "Net-(D1-C)") (class "Default")
      (node (ref "D1") (pin "1") (pinfunction "C_1") (pintype "passive"))
      (node (ref "U11") (pin "3") (pinfunction "VIN_3") (pintype "input"))
    )
    (net (code "105") (name "Net-(D3-PadA)") (class "Default")
      (node (ref "D3") (pin "A") (pinfunction "A_A") (pintype "passive"))
      (node (ref "R21") (pin "1") (pinfunction "1_1") (pintype "passive"))
    )
    (net (code "106") (name "Net-(D6-PadA)") (class "Default")
      (node (ref "D6") (pin "A") (pinfunction "A_A") (pintype "passive"))
      (node (ref "R118") (pin "2") (pinfunction "2_2") (pintype "passive"))
    )
    (net (code "107") (name "Net-(D14-PadA)") (class "Default")
      (node (ref "D14") (pin "A") (pinfunction "A_A") (pintype "passive"))
      (node (ref "R30") (pin "1") (pinfunction "1_1") (pintype "passive"))
    )
    (net (code "108") (name "Net-(D15-PadA)") (class "Default")
      (node (ref "D15") (pin "A") (pinfunction "A_A") (pintype "passive"))
      (node (ref "R167") (pin "1") (pinfunction "1_1") (pintype "passive"))
    )
    (net (code "109") (name "Net-(D16-PadA)") (class "Default")
      (node (ref "D16") (pin "A") (pinfunction "A_A") (pintype "passive"))
      (node (ref "R169") (pin "1") (pinfunction "1_1") (pintype "passive"))
    )
    (net (code "110") (name "Net-(D17-A)") (class "Default")
      (node (ref "D17") (pin "2") (pinfunction "A_2") (pintype "passive"))
      (node (ref "D8") (pin "2") (pinfunction "A_2") (pintype "passive"))
      (node (ref "Fuse1") (pin "2") (pinfunction "2_2") (pintype "passive"))
    )
    (net (code "111") (name "Net-(F1-Pad2)") (class "Default")
      (node (ref "F1") (pin "2") (pinfunction "2_2") (pintype "passive"))
      (node (ref "J1") (pin "1") (pinfunction "1_1") (pintype "passive"))
    )
    (net (code "112") (name "Net-(IC2-PB2)") (class "Default")
      (node (ref "IC2") (pin "37") (pinfunction "PB2_37") (pintype "bidirectional"))
      (node (ref "R3") (pin "1") (pinfunction "1_1") (pintype "passive"))
    )
    (net (code "113") (name "Net-(IC2-PC9)") (class "Default")
      (node (ref "IC2") (pin "66") (pinfunction "PC9_66") (pintype "bidirectional"))
      (node (ref "R174") (pin "1") (pinfunction "1_1") (pintype "passive"))
    )
    (net (code "114") (name "Net-(IC2-VDDA)") (class "Default")
      (node (ref "C37") (pin "2") (pinfunction "2_2") (pintype "passive"))
      (node (ref "C77") (pin "2") (pinfunction "2_2") (pintype "passive"))
      (node (ref "IC2") (pin "22") (pinfunction "VDDA_22") (pintype "bidirectional"))
      (node (ref "L1") (pin "2") (pinfunction "2_2") (pintype "passive"))
    )
    (net (code "115") (name "Net-(IC3-BOOT)") (class "Default")
      (node (ref "IC3") (pin "1") (pinfunction "BOOT_1") (pintype "output"))
      (node (ref "R191") (pin "1") (pinfunction "1_1") (pintype "passive"))
    )
    (net (code "116") (name "Net-(IC3-COMP)") (class "Default")
      (node (ref "C74") (pin "2") (pinfunction "2_2") (pintype "passive"))
      (node (ref "IC3") (pin "6") (pinfunction "COMP_6") (pintype "output"))
      (node (ref "R119") (pin "2") (pinfunction "2_2") (pintype "passive"))
    )
    (net (code "117") (name "Net-(IC3-EN)") (class "Default")
      (node (ref "IC3") (pin "3") (pinfunction "EN_3") (pintype "input"))
      (node (ref "R120") (pin "2") (pinfunction "2_2") (pintype "passive"))
      (node (ref "R34") (pin "1") (pinfunction "1_1") (pintype "passive"))
    )
    (net (code "118") (name "Net-(IC3-FB)") (class "Default")
      (node (ref "IC3") (pin "5") (pinfunction "FB_5") (pintype "input"))
      (node (ref "R122") (pin "2") (pinfunction "2_2") (pintype "passive"))
      (node (ref "R36") (pin "1") (pinfunction "1_1") (pintype "passive"))
    )
    (net (code "119") (name "Net-(IC3-RT{slash}CLK)") (class "Default")
      (node (ref "IC3") (pin "4") (pinfunction "RT/CLK_4") (pintype "input"))
      (node (ref "R121") (pin "2") (pinfunction "2_2") (pintype "passive"))
    )
    (net (code "120") (name "Net-(IC3-SW)") (class "Default")
      (node (ref "C17") (pin "2") (pinfunction "2_2") (pintype "passive"))
      (node (ref "C93") (pin "1") (pinfunction "1_1") (pintype "passive"))
      (node (ref "D2") (pin "K") (pinfunction "K_K") (pintype "passive"))
      (node (ref "IC3") (pin "8") (pinfunction "SW_8") (pintype "input"))
      (node (ref "L5") (pin "1") (pinfunction "1_1") (pintype "passive"))
    )
    (net (code "121") (name "Net-(IC3-VIN)") (class "Default")
      (node (ref "C19") (pin "2") (pinfunction "2_2") (pintype "passive"))
      (node (ref "C27") (pin "2") (pinfunction "2_2") (pintype "passive"))
      (node (ref "C94") (pin "2") (pinfunction "2_2") (pintype "passive"))
      (node (ref "IC3") (pin "2") (pinfunction "VIN_2") (pintype "input"))
      (node (ref "L4") (pin "2") (pinfunction "2_2") (pintype "passive"))
      (node (ref "R34") (pin "2") (pinfunction "2_2") (pintype "passive"))
    )
    (net (code "122") (name "Net-(J2-VCC)") (class "Default")
      (node (ref "J1") (pin "2") (pinfunction "2_2") (pintype "passive"))
      (node (ref "J2") (pin "1") (pinfunction "VCC_1") (pintype "power_in"))
    )
    (net (code "123") (name "Net-(J4-VCC)") (class "Default")
      (node (ref "C13") (pin "2") (pinfunction "2_2") (pintype "passive"))
      (node (ref "J4") (pin "01") (pinfunction "VCC_01") (pintype "power_in"))
      (node (ref "L3") (pin "2") (pinfunction "2_2") (pintype "passive"))
      (node (ref "R18") (pin "2") (pinfunction "2_2") (pintype "passive"))
    )
    (net (code "124") (name "Net-(J47-Pad2)") (class "Default")
      (node (ref "J47") (pin "2") (pinfunction "2_2") (pintype "passive"))
      (node (ref "R175") (pin "2") (pinfunction "2_2") (pintype "passive"))
      (node (ref "R29") (pin "1") (pinfunction "1_1") (pintype "passive"))
    )
    (net (code "125") (name "Net-(L2-Pad2)") (class "Default")
      (node (ref "L2") (pin "2") (pinfunction "2_2") (pintype "passive"))
      (node (ref "R13") (pin "1") (pinfunction "1_1") (pintype "passive"))
    )
    (net (code "126") (name "Net-(Q6-DRAIN)") (class "Default")
      (node (ref "D7") (pin "A") (pinfunction "A_A") (pintype "passive"))
      (node (ref "Q6") (pin "TAB") (pinfunction "DRAIN_TAB") (pintype "passive"))
      (node (ref "Q7") (pin "3") (pinfunction "C_3") (pintype "passive"))
      (node (ref "RLY1") (pin "2") (pinfunction "COIL2_2") (pintype "passive"))
    )
    (net (code "127") (name "Net-(Q6-GATE)") (class "Default")
      (node (ref "Q6") (pin "1") (pinfunction "GATE_1") (pintype "passive"))
      (node (ref "Q7") (pin "1") (pinfunction "B_1") (pintype "passive"))
      (node (ref "R123") (pin "2") (pinfunction "2_2") (pintype "passive"))
    )
    (net (code "128") (name "Net-(Q19-G)") (class "Default")
      (node (ref "Q19") (pin "1") (pinfunction "G_1") (pintype "passive"))
      (node (ref "R4") (pin "2") (pinfunction "2_2") (pintype "passive"))
    )
    (net (code "129") (name "Net-(Q19-S)") (class "Default")
      (node (ref "Q19") (pin "2") (pinfunction "S_2") (pintype "passive"))
      (node (ref "R5") (pin "2") (pinfunction "2_2") (pintype "passive"))
    )
    (net (code "130") (name "unconnected-(IC2-PB12-Pad51)") (class "Default")
      (node (ref "IC2") (pin "51") (pinfunction "PB12_51") (pintype "bidirectional"))
    )
    (net (code "131") (name "unconnected-(IC2-VBAT-Pad6)") (class "Default")
      (node (ref "IC2") (pin "6") (pinfunction "VBAT_6") (pintype "bidirectional"))
    )
    (net (code "132") (name "unconnected-(J1-Pad3)") (class "Default")
      (node (ref "J1") (pin "3") (pinfunction "3_3") (pintype "passive"))
    )
    (net (code "133") (name "unconnected-(J20-Pad10)") (class "Default")
      (node (ref "J20") (pin "10") (pinfunction "10_10") (pintype "passive"))
    )
    (net (code "134") (name "unconnected-(J20-PadP1)") (class "Default")
      (node (ref "J20") (pin "P1") (pinfunction "P1_P1") (pintype "passive"))
    )
    (net (code "135") (name "unconnected-(J20-PadP2)") (class "Default")
      (node (ref "J20") (pin "P2") (pinfunction "P2_P2") (pintype "passive"))
    )
    (net (code "136") (name "unconnected-(J47-Pad1)") (class "Default")
      (node (ref "J47") (pin "1") (pinfunction "1_1") (pintype "passive"))
    )
    (net (code "137") (name "unconnected-(J47-Pad8)") (class "Default")
      (node (ref "J47") (pin "8") (pinfunction "8_8") (pintype "passive"))
    )
    (net (code "138") (name "unconnected-(RLY1-NC-Pad4)") (class "Default")
      (node (ref "RLY1") (pin "4") (pinfunction "NC_4") (pintype "passive"))
    )
  )
)
